# bontor_mbed_rev_e.net
KiCad netlist of a schematic drawn in EAGLE
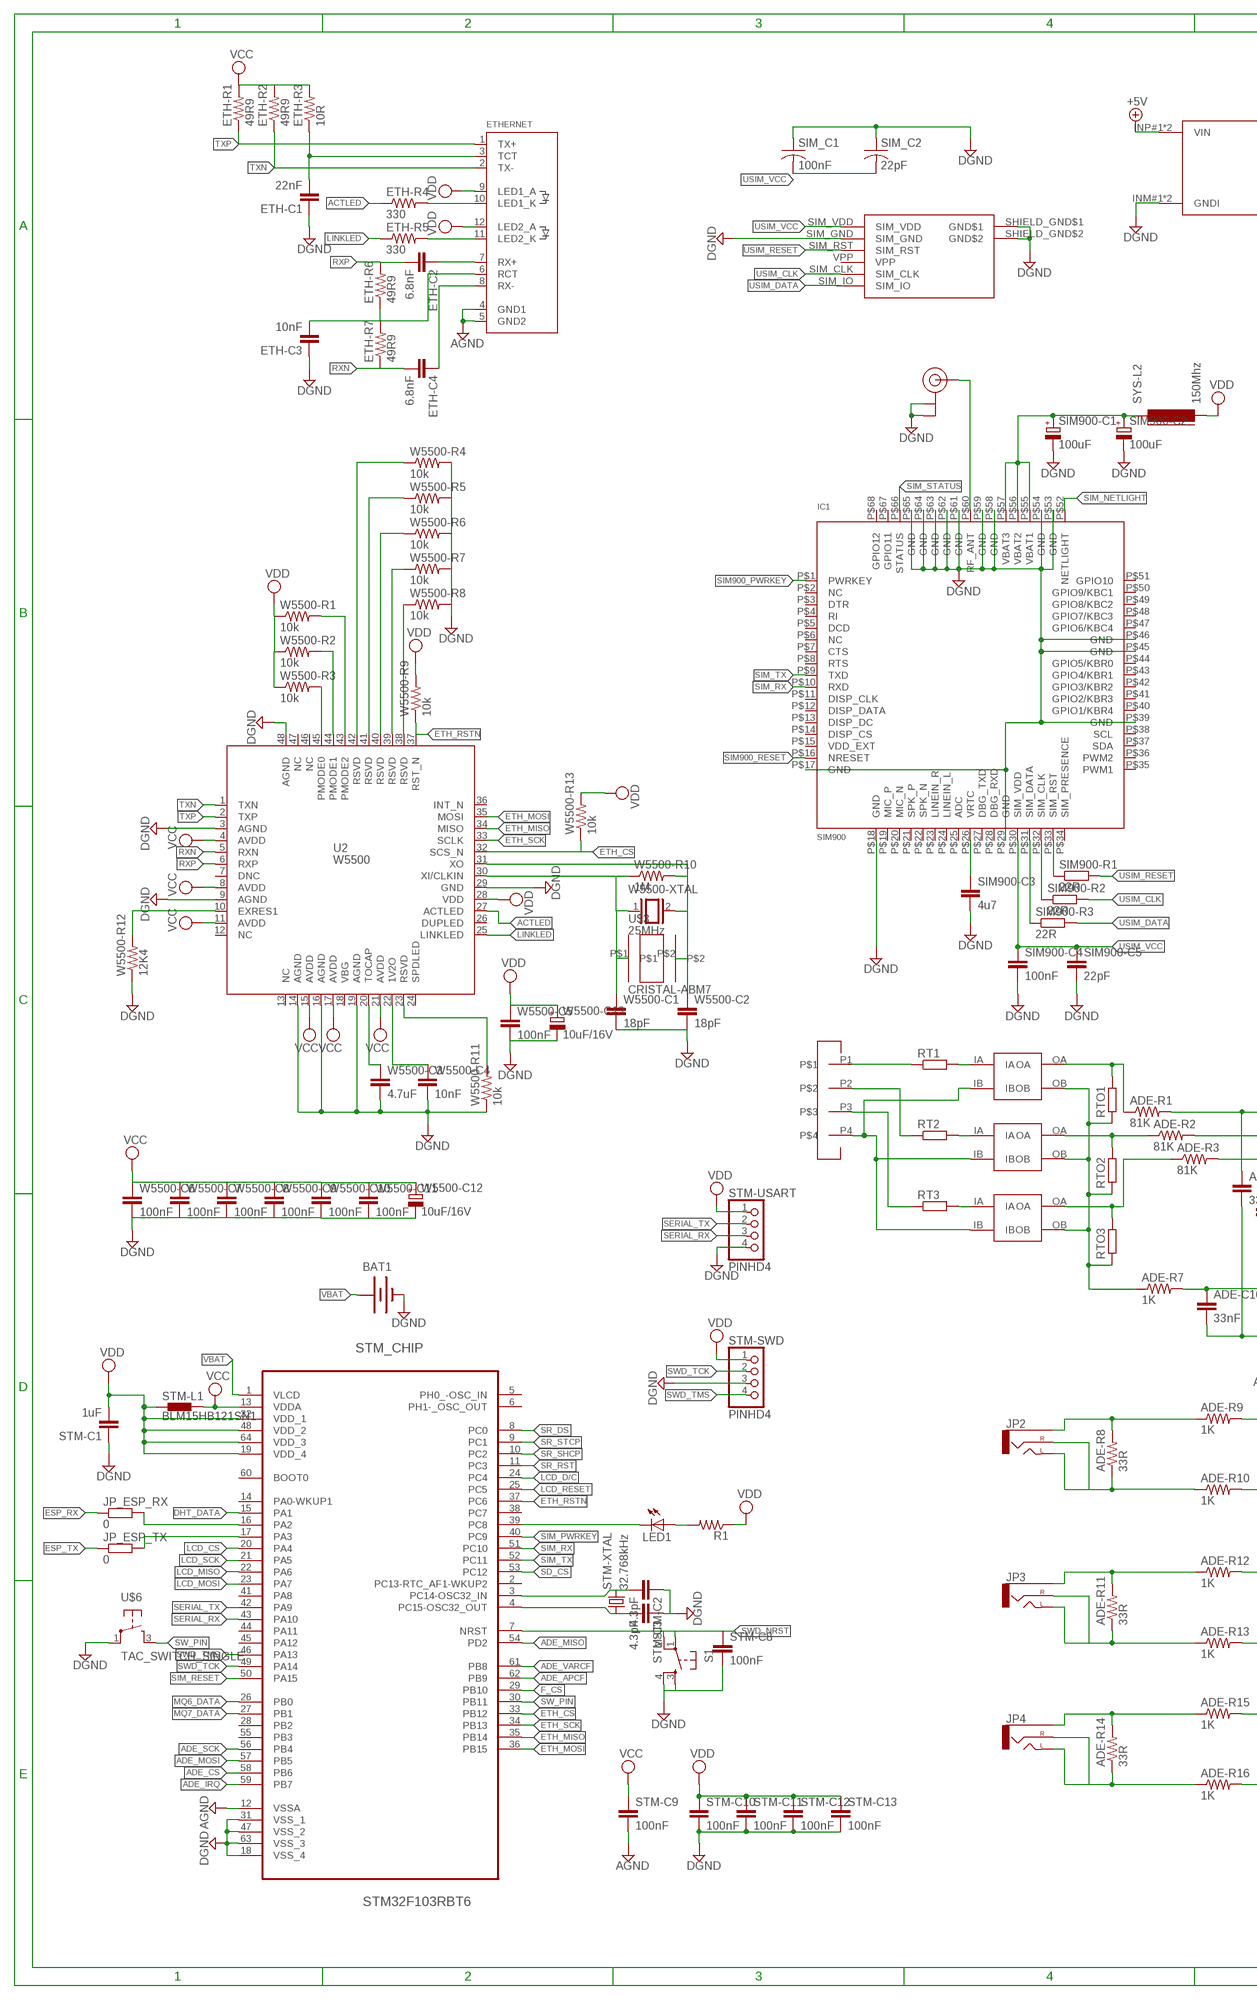
[diagram p0: schematic, sheet 1, part 1 of 2]
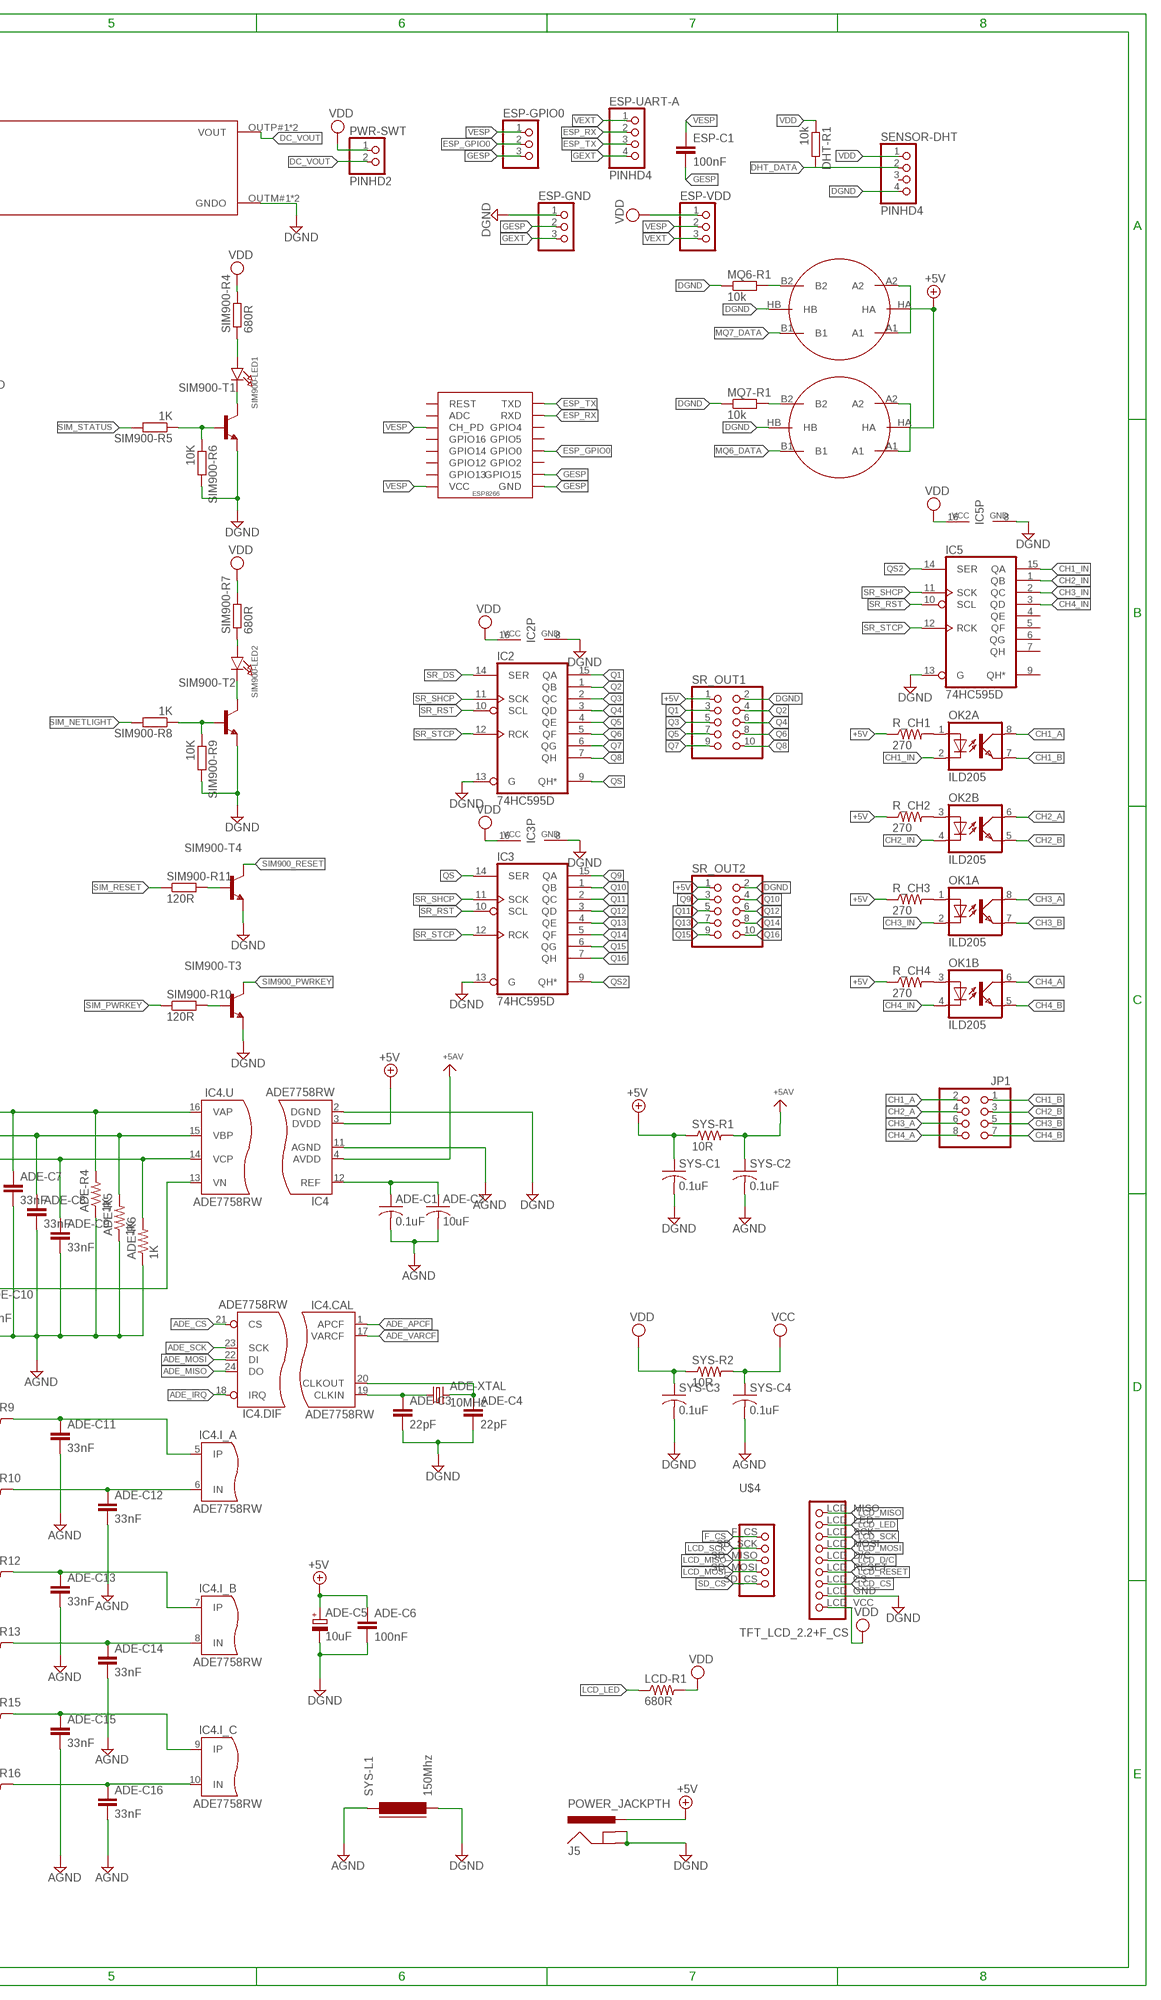
[diagram p1: schematic, sheet 1, part 2 of 2]

(export (version "E")
  (design (tool "Eeschema 10.0.6"))
  (components
    (comp (ref "ADE-C1")
      (value "0.1uF")
      (footprint "eagle-import:C0603@1")
      (libsource (lib "eagle-import") (part "C-USC0603"))
    )
    (comp (ref "ADE-C2")
      (value "10uF")
      (footprint "eagle-import:C0805K")
      (libsource (lib "eagle-import") (part "C-USC0805K"))
    )
    (comp (ref "ADE-C3")
      (value "22pF")
      (footprint "eagle-import:C0603")
      (libsource (lib "eagle-import") (part "C-EUC0603"))
    )
    (comp (ref "ADE-C4")
      (value "22pF")
      (footprint "eagle-import:C0603")
      (libsource (lib "eagle-import") (part "C-EUC0603"))
    )
    (comp (ref "ADE-C5")
      (value "10uF")
      (footprint "eagle-import:153CLV-0605")
      (libsource (lib "eagle-import") (part "CPOL-EU153CLV-0605"))
    )
    (comp (ref "ADE-C6")
      (value "100nF")
      (footprint "eagle-import:C0603")
      (libsource (lib "eagle-import") (part "C-EUC0603"))
    )
    (comp (ref "ADE-C7")
      (value "33nF")
      (footprint "eagle-import:0603-CAP")
      (libsource (lib "eagle-import") (part "CAP0603-CAP"))
    )
    (comp (ref "ADE-C8")
      (value "33nF")
      (footprint "eagle-import:0603-CAP")
      (libsource (lib "eagle-import") (part "CAP0603-CAP"))
    )
    (comp (ref "ADE-C9")
      (value "33nF")
      (footprint "eagle-import:0603-CAP")
      (libsource (lib "eagle-import") (part "CAP0603-CAP"))
    )
    (comp (ref "ADE-C10")
      (value "33nF")
      (footprint "eagle-import:0603-CAP")
      (libsource (lib "eagle-import") (part "CAP0603-CAP"))
    )
    (comp (ref "ADE-C11")
      (value "33nF")
      (footprint "eagle-import:0603-CAP")
      (libsource (lib "eagle-import") (part "CAP0603-CAP"))
    )
    (comp (ref "ADE-C12")
      (value "33nF")
      (footprint "eagle-import:0603-CAP")
      (libsource (lib "eagle-import") (part "CAP0603-CAP"))
    )
    (comp (ref "ADE-C13")
      (value "33nF")
      (footprint "eagle-import:0603-CAP")
      (libsource (lib "eagle-import") (part "CAP0603-CAP"))
    )
    (comp (ref "ADE-C14")
      (value "33nF")
      (footprint "eagle-import:0603-CAP")
      (libsource (lib "eagle-import") (part "CAP0603-CAP"))
    )
    (comp (ref "ADE-C15")
      (value "33nF")
      (footprint "eagle-import:0603-CAP")
      (libsource (lib "eagle-import") (part "CAP0603-CAP"))
    )
    (comp (ref "ADE-C16")
      (value "33nF")
      (footprint "eagle-import:0603-CAP")
      (libsource (lib "eagle-import") (part "CAP0603-CAP"))
    )
    (comp (ref "ADE-R1")
      (value "81K")
      (footprint "eagle-import:0603-RES")
      (libsource (lib "eagle-import") (part "SparkFun-Passives_RESISTOR0603-RES"))
    )
    (comp (ref "ADE-R2")
      (value "81K")
      (footprint "eagle-import:0603-RES")
      (libsource (lib "eagle-import") (part "SparkFun-Passives_RESISTOR0603-RES"))
    )
    (comp (ref "ADE-R3")
      (value "81K")
      (footprint "eagle-import:0603-RES")
      (libsource (lib "eagle-import") (part "SparkFun-Passives_RESISTOR0603-RES"))
    )
    (comp (ref "ADE-R4")
      (value "1K")
      (footprint "eagle-import:0603-RES")
      (libsource (lib "eagle-import") (part "SparkFun-Passives_RESISTOR0603-RES"))
    )
    (comp (ref "ADE-R5")
      (value "1K")
      (footprint "eagle-import:0603-RES")
      (libsource (lib "eagle-import") (part "SparkFun-Passives_RESISTOR0603-RES"))
    )
    (comp (ref "ADE-R6")
      (value "1K")
      (footprint "eagle-import:0603-RES")
      (libsource (lib "eagle-import") (part "SparkFun-Passives_RESISTOR0603-RES"))
    )
    (comp (ref "ADE-R7")
      (value "1K")
      (footprint "eagle-import:0603-RES")
      (libsource (lib "eagle-import") (part "SparkFun-Passives_RESISTOR0603-RES"))
    )
    (comp (ref "ADE-R8")
      (value "33R")
      (footprint "eagle-import:0603-RES")
      (libsource (lib "eagle-import") (part "SparkFun-Passives_RESISTOR0603-RES"))
    )
    (comp (ref "ADE-R9")
      (value "1K")
      (footprint "eagle-import:0603-RES")
      (libsource (lib "eagle-import") (part "SparkFun-Passives_RESISTOR0603-RES"))
    )
    (comp (ref "ADE-R10")
      (value "1K")
      (footprint "eagle-import:0603-RES")
      (libsource (lib "eagle-import") (part "SparkFun-Passives_RESISTOR0603-RES"))
    )
    (comp (ref "ADE-R11")
      (value "33R")
      (footprint "eagle-import:0603-RES")
      (libsource (lib "eagle-import") (part "SparkFun-Passives_RESISTOR0603-RES"))
    )
    (comp (ref "ADE-R12")
      (value "1K")
      (footprint "eagle-import:0603-RES")
      (libsource (lib "eagle-import") (part "SparkFun-Passives_RESISTOR0603-RES"))
    )
    (comp (ref "ADE-R13")
      (value "1K")
      (footprint "eagle-import:0603-RES")
      (libsource (lib "eagle-import") (part "SparkFun-Passives_RESISTOR0603-RES"))
    )
    (comp (ref "ADE-R14")
      (value "33R")
      (footprint "eagle-import:0603-RES")
      (libsource (lib "eagle-import") (part "SparkFun-Passives_RESISTOR0603-RES"))
    )
    (comp (ref "ADE-R15")
      (value "1K")
      (footprint "eagle-import:0603-RES")
      (libsource (lib "eagle-import") (part "SparkFun-Passives_RESISTOR0603-RES"))
    )
    (comp (ref "ADE-R16")
      (value "1K")
      (footprint "eagle-import:0603-RES")
      (libsource (lib "eagle-import") (part "SparkFun-Passives_RESISTOR0603-RES"))
    )
    (comp (ref "ADE-XTAL")
      (value "10MHz")
      (footprint "eagle-import:HC49US")
      (libsource (lib "eagle-import") (part "CRYSTALHC49US"))
    )
    (comp (ref "BAT1")
      (value "BATTERY20PTH")
      (footprint "eagle-import:BATTCOM_20MM_PTH")
      (libsource (lib "eagle-import") (part "BATTERY20PTH"))
    )
    (comp (ref "DCDC-3.5V")
      (value "DCDCMODULE_SMALL")
      (footprint "eagle-import:DCDCMODULE-SMALL")
      (libsource (lib "eagle-import") (part "DCDCMODULE_SMALL"))
    )
    (comp (ref "DHT-R1")
      (value "10k")
      (footprint "eagle-import:R0603")
      (libsource (lib "eagle-import") (part "resistor_R-EU_R0603"))
    )
    (comp (ref "ESP-C1")
      (value "100nF")
      (footprint "eagle-import:C0603")
      (libsource (lib "eagle-import") (part "C-EUC0603"))
    )
    (comp (ref "ESP-GND")
      (value "PINHD-1X3")
      (footprint "eagle-import:1X03")
      (libsource (lib "eagle-import") (part "PINHD-1X3"))
    )
    (comp (ref "ESP-GPIO0")
      (value "PINHD-1X3")
      (footprint "eagle-import:1X03")
      (libsource (lib "eagle-import") (part "PINHD-1X3"))
    )
    (comp (ref "ESP-UART-A")
      (value "PINHD4")
      (footprint "eagle-import:PINHD4")
      (libsource (lib "eagle-import") (part "PINHD4"))
    )
    (comp (ref "ESP-VDD")
      (value "PINHD-1X3")
      (footprint "eagle-import:1X03")
      (libsource (lib "eagle-import") (part "PINHD-1X3"))
    )
    (comp (ref "ETH-C1")
      (value "22nF")
      (footprint "eagle-import:C0603")
      (libsource (lib "eagle-import") (part "C-EUC0603"))
    )
    (comp (ref "ETH-C2")
      (value "6.8nF")
      (footprint "eagle-import:C0603")
      (libsource (lib "eagle-import") (part "C-EUC0603"))
    )
    (comp (ref "ETH-C3")
      (value "10nF")
      (footprint "eagle-import:C0603")
      (libsource (lib "eagle-import") (part "C-EUC0603"))
    )
    (comp (ref "ETH-C4")
      (value "6.8nF")
      (footprint "eagle-import:C0603")
      (libsource (lib "eagle-import") (part "C-EUC0603"))
    )
    (comp (ref "ETH-R1")
      (value "49R9")
      (footprint "eagle-import:R0603")
      (libsource (lib "eagle-import") (part "R-US_R0603"))
    )
    (comp (ref "ETH-R2")
      (value "49R9")
      (footprint "eagle-import:R0603")
      (libsource (lib "eagle-import") (part "R-US_R0603"))
    )
    (comp (ref "ETH-R3")
      (value "10R")
      (footprint "eagle-import:R0603")
      (libsource (lib "eagle-import") (part "R-US_R0603"))
    )
    (comp (ref "ETH-R4")
      (value "330")
      (footprint "eagle-import:R0603")
      (libsource (lib "eagle-import") (part "R-US_R0603"))
    )
    (comp (ref "ETH-R5")
      (value "330")
      (footprint "eagle-import:R0603")
      (libsource (lib "eagle-import") (part "R-US_R0603"))
    )
    (comp (ref "ETH-R6")
      (value "49R9")
      (footprint "eagle-import:R0603")
      (libsource (lib "eagle-import") (part "R-US_R0603"))
    )
    (comp (ref "ETH-R7")
      (value "49R9")
      (footprint "eagle-import:R0603")
      (libsource (lib "eagle-import") (part "R-US_R0603"))
    )
    (comp (ref "ETHERNET")
      (value "RJ45J0026D21BNL")
      (footprint "eagle-import:RJ45_PULSEJACK")
      (libsource (lib "eagle-import") (part "RJ45J0026D21BNL"))
    )
    (comp (ref "IC1")
      (value "SIM900")
      (footprint "eagle-import:SIM900_SMT")
      (libsource (lib "eagle-import") (part "GSM_SIM900_LITERAL"))
    )
    (comp (ref "IC2")
      (value "74HC595D")
      (footprint "eagle-import:SO16")
      (libsource (lib "eagle-import") (part "74595DHC"))
    )
    (comp (ref "IC3")
      (value "74HC595D")
      (footprint "eagle-import:SO16")
      (libsource (lib "eagle-import") (part "74595DHC"))
    )
    (comp (ref "IC4")
      (value "ADE7758RW")
      (footprint "eagle-import:SOIC24")
      (libsource (lib "eagle-import") (part "ADE7758RW"))
    )
    (comp (ref "IC5")
      (value "74HC595D")
      (footprint "eagle-import:SO16")
      (libsource (lib "eagle-import") (part "74595DHC"))
    )
    (comp (ref "J5")
      (value "POWER_JACKPTH")
      (footprint "eagle-import:POWER_JACK_PTH")
      (libsource (lib "eagle-import") (part "POWER_JACKPTH"))
    )
    (comp (ref "JP1")
      (value "PINHD-2X4")
      (footprint "eagle-import:2X04")
      (libsource (lib "eagle-import") (part "PINHD-2X4"))
    )
    (comp (ref "JP2")
      (value "AUDIO-JACKSMD2")
      (footprint "eagle-import:AUDIO-JACK-3.5MM-SMD")
      (libsource (lib "eagle-import") (part "AUDIO-JACKSMD2"))
    )
    (comp (ref "JP3")
      (value "AUDIO-JACKSMD2")
      (footprint "eagle-import:AUDIO-JACK-3.5MM-SMD")
      (libsource (lib "eagle-import") (part "AUDIO-JACKSMD2"))
    )
    (comp (ref "JP4")
      (value "AUDIO-JACKSMD2")
      (footprint "eagle-import:AUDIO-JACK-3.5MM-SMD")
      (libsource (lib "eagle-import") (part "AUDIO-JACKSMD2"))
    )
    (comp (ref "JP_ESP_RX")
      (value "0")
      (footprint "eagle-import:R0201")
      (libsource (lib "eagle-import") (part "R-EU_R0201"))
    )
    (comp (ref "JP_ESP_TX")
      (value "0")
      (footprint "eagle-import:R0201")
      (libsource (lib "eagle-import") (part "R-EU_R0201"))
    )
    (comp (ref "LCD-R1")
      (value "680R")
      (footprint "eagle-import:0603-RES")
      (libsource (lib "eagle-import") (part "SparkFun-Passives_RESISTOR0603-RES"))
    )
    (comp (ref "LED1")
      (value "LEDCHIPLED_0603")
      (footprint "eagle-import:CHIPLED_0603")
      (libsource (lib "eagle-import") (part "LEDCHIPLED_0603"))
    )
    (comp (ref "MQ6-R1")
      (value "10k")
      (footprint "eagle-import:R0603")
      (libsource (lib "eagle-import") (part "resistor_R-EU_R0603"))
    )
    (comp (ref "MQ7-R1")
      (value "10k")
      (footprint "eagle-import:R0603")
      (libsource (lib "eagle-import") (part "resistor_R-EU_R0603"))
    )
    (comp (ref "OK1")
      (value "ILD205")
      (footprint "eagle-import:SOIC08")
      (fields (field (name "MF") "VISHAY/TELEFUNKEN") (field (name "MPN") "ILD205T"))
      (libsource (lib "eagle-import") (part "ILD205"))
    )
    (comp (ref "OK2")
      (value "ILD205")
      (footprint "eagle-import:SOIC08")
      (fields (field (name "MF") "VISHAY/TELEFUNKEN") (field (name "MPN") "ILD205T"))
      (libsource (lib "eagle-import") (part "ILD205"))
    )
    (comp (ref "PWR-SWT")
      (value "PINHD2")
      (footprint "eagle-import:PINHD2")
      (libsource (lib "eagle-import") (part "PINHD2"))
    )
    (comp (ref "R1")
      (value "RESISTOR0603-RES")
      (footprint "eagle-import:0603-RES")
      (libsource (lib "eagle-import") (part "RESISTOR0603-RES"))
    )
    (comp (ref "RT1")
      (value "R-EU_0309/V")
      (footprint "eagle-import:0309V")
      (libsource (lib "eagle-import") (part "R-EU_0309/V"))
    )
    (comp (ref "RT2")
      (value "R-EU_0309/V")
      (footprint "eagle-import:0309V")
      (libsource (lib "eagle-import") (part "R-EU_0309/V"))
    )
    (comp (ref "RT3")
      (value "R-EU_0309/V")
      (footprint "eagle-import:0309V")
      (libsource (lib "eagle-import") (part "R-EU_0309/V"))
    )
    (comp (ref "RTO1")
      (value "R-EU_0309/12")
      (footprint "eagle-import:0309_12")
      (libsource (lib "eagle-import") (part "R-EU_0309/12"))
    )
    (comp (ref "RTO2")
      (value "R-EU_0309/12")
      (footprint "eagle-import:0309_12")
      (libsource (lib "eagle-import") (part "R-EU_0309/12"))
    )
    (comp (ref "RTO3")
      (value "R-EU_0309/12")
      (footprint "eagle-import:0309_12")
      (libsource (lib "eagle-import") (part "R-EU_0309/12"))
    )
    (comp (ref "R_CH1")
      (value "270")
      (footprint "eagle-import:0603-RES")
      (libsource (lib "eagle-import") (part "SparkFun-Passives_RESISTOR0603-RES"))
    )
    (comp (ref "R_CH2")
      (value "270")
      (footprint "eagle-import:0603-RES")
      (libsource (lib "eagle-import") (part "SparkFun-Passives_RESISTOR0603-RES"))
    )
    (comp (ref "R_CH3")
      (value "270")
      (footprint "eagle-import:0603-RES")
      (libsource (lib "eagle-import") (part "SparkFun-Passives_RESISTOR0603-RES"))
    )
    (comp (ref "R_CH4")
      (value "270")
      (footprint "eagle-import:0603-RES")
      (libsource (lib "eagle-import") (part "SparkFun-Passives_RESISTOR0603-RES"))
    )
    (comp (ref "S1")
      (value "TAC_SWITCHPTH")
      (footprint "eagle-import:TACTILE-PTH")
      (libsource (lib "eagle-import") (part "TAC_SWITCHPTH"))
    )
    (comp (ref "SENSOR-DHT")
      (value "PINHD4")
      (footprint "eagle-import:PINHD4")
      (libsource (lib "eagle-import") (part "PINHD4"))
    )
    (comp (ref "SENSOR-MQ6")
      (value "METHANE_SENSOR")
      (footprint "eagle-import:MQ-3")
      (libsource (lib "eagle-import") (part "METHANE_SENSOR"))
    )
    (comp (ref "SENSOR-MQ7")
      (value "METHANE_SENSOR")
      (footprint "eagle-import:MQ-3")
      (libsource (lib "eagle-import") (part "METHANE_SENSOR"))
    )
    (comp (ref "SIM900-C1")
      (value "100uF")
      (footprint "eagle-import:153CLV-0605")
      (libsource (lib "eagle-import") (part "CPOL-EU153CLV-0605"))
    )
    (comp (ref "SIM900-C2")
      (value "100uF")
      (footprint "eagle-import:153CLV-0605")
      (libsource (lib "eagle-import") (part "CPOL-EU153CLV-0605"))
    )
    (comp (ref "SIM900-C3")
      (value "4u7")
      (footprint "eagle-import:C0603")
      (libsource (lib "eagle-import") (part "C-EUC0603"))
    )
    (comp (ref "SIM900-C4")
      (value "100nF")
      (footprint "eagle-import:C0603")
      (libsource (lib "eagle-import") (part "C-EUC0603"))
    )
    (comp (ref "SIM900-C5")
      (value "22pF")
      (footprint "eagle-import:C0603")
      (libsource (lib "eagle-import") (part "C-EUC0603"))
    )
    (comp (ref "SIM900-LED1")
      (value "LED0805_NOOUTLINE")
      (footprint "eagle-import:CHIPLED_0805_NOOUTLINE")
      (libsource (lib "eagle-import") (part "LED0805_NOOUTLINE"))
    )
    (comp (ref "SIM900-LED2")
      (value "LED0805_NOOUTLINE")
      (footprint "eagle-import:CHIPLED_0805_NOOUTLINE")
      (libsource (lib "eagle-import") (part "LED0805_NOOUTLINE"))
    )
    (comp (ref "SIM900-R1")
      (value "22R")
      (footprint "eagle-import:R0603")
      (libsource (lib "eagle-import") (part "R-EU_R0603"))
    )
    (comp (ref "SIM900-R2")
      (value "22R")
      (footprint "eagle-import:R0603")
      (libsource (lib "eagle-import") (part "R-EU_R0603"))
    )
    (comp (ref "SIM900-R3")
      (value "22R")
      (footprint "eagle-import:R0603")
      (libsource (lib "eagle-import") (part "R-EU_R0603"))
    )
    (comp (ref "SIM900-R4")
      (value "680R")
      (footprint "eagle-import:R0603")
      (libsource (lib "eagle-import") (part "R-EU_R0603"))
    )
    (comp (ref "SIM900-R5")
      (value "1K")
      (footprint "eagle-import:R0603")
      (libsource (lib "eagle-import") (part "R-EU_R0603"))
    )
    (comp (ref "SIM900-R6")
      (value "10K")
      (footprint "eagle-import:R0603")
      (libsource (lib "eagle-import") (part "R-EU_R0603"))
    )
    (comp (ref "SIM900-R7")
      (value "680R")
      (footprint "eagle-import:R0603")
      (libsource (lib "eagle-import") (part "R-EU_R0603"))
    )
    (comp (ref "SIM900-R8")
      (value "1K")
      (footprint "eagle-import:R0603")
      (libsource (lib "eagle-import") (part "R-EU_R0603"))
    )
    (comp (ref "SIM900-R9")
      (value "10K")
      (footprint "eagle-import:R0603")
      (libsource (lib "eagle-import") (part "R-EU_R0603"))
    )
    (comp (ref "SIM900-R10")
      (value "120R")
      (footprint "eagle-import:R0603")
      (libsource (lib "eagle-import") (part "resistor_R-EU_R0603"))
    )
    (comp (ref "SIM900-R11")
      (value "120R")
      (footprint "eagle-import:R0603")
      (libsource (lib "eagle-import") (part "resistor_R-EU_R0603"))
    )
    (comp (ref "SIM900-T1")
      (value "MMBT2222ALT1-NPN-SOT23-BEC")
      (footprint "eagle-import:SOT23-BEC")
      (libsource (lib "eagle-import") (part "-NPN-SOT23-BECMMBT2222ALT1"))
    )
    (comp (ref "SIM900-T2")
      (value "MMBT2222ALT1-NPN-SOT23-BEC")
      (footprint "eagle-import:SOT23-BEC")
      (libsource (lib "eagle-import") (part "-NPN-SOT23-BECMMBT2222ALT1"))
    )
    (comp (ref "SIM900-T3")
      (value "MMBT2222ALT1-NPN-SOT23-BEC")
      (footprint "eagle-import:SOT23-BEC")
      (libsource (lib "eagle-import") (part "transistor-neu-to92_-NPN-SOT23-BECMMBT2222ALT1"))
    )
    (comp (ref "SIM900-T4")
      (value "MMBT2222ALT1-NPN-SOT23-BEC")
      (footprint "eagle-import:SOT23-BEC")
      (libsource (lib "eagle-import") (part "transistor-neu-to92_-NPN-SOT23-BECMMBT2222ALT1"))
    )
    (comp (ref "SIM_C1")
      (value "100nF")
      (footprint "eagle-import:C0603K")
      (libsource (lib "eagle-import") (part "C-USC0603K"))
    )
    (comp (ref "SIM_C2")
      (value "22pF")
      (footprint "eagle-import:C0603K")
      (libsource (lib "eagle-import") (part "C-USC0603K"))
    )
    (comp (ref "SR_OUT1")
      (value "PINHD-2X5/90")
      (footprint "eagle-import:2X05_90")
      (libsource (lib "eagle-import") (part "PINHD-2X5/90"))
    )
    (comp (ref "SR_OUT2")
      (value "PINHD-2X5/90")
      (footprint "eagle-import:2X05_90")
      (libsource (lib "eagle-import") (part "PINHD-2X5/90"))
    )
    (comp (ref "STM-C1")
      (value "1uF")
      (footprint "eagle-import:C0603")
      (libsource (lib "eagle-import") (part "C-EUC0603"))
    )
    (comp (ref "STM-C2")
      (value "4.3pF")
      (footprint "eagle-import:C0603")
      (libsource (lib "eagle-import") (part "C-EUC0603"))
    )
    (comp (ref "STM-C3")
      (value "4.3pF")
      (footprint "eagle-import:C0603")
      (libsource (lib "eagle-import") (part "C-EUC0603"))
    )
    (comp (ref "STM-C8")
      (value "100nF")
      (footprint "eagle-import:C0603")
      (libsource (lib "eagle-import") (part "C-EUC0603"))
    )
    (comp (ref "STM-C9")
      (value "100nF")
      (footprint "eagle-import:C0603")
      (libsource (lib "eagle-import") (part "C-EUC0603"))
    )
    (comp (ref "STM-C10")
      (value "100nF")
      (footprint "eagle-import:C0603")
      (libsource (lib "eagle-import") (part "C-EUC0603"))
    )
    (comp (ref "STM-C11")
      (value "100nF")
      (footprint "eagle-import:C0603")
      (libsource (lib "eagle-import") (part "C-EUC0603"))
    )
    (comp (ref "STM-C12")
      (value "100nF")
      (footprint "eagle-import:C0603")
      (libsource (lib "eagle-import") (part "C-EUC0603"))
    )
    (comp (ref "STM-C13")
      (value "100nF")
      (footprint "eagle-import:C0603")
      (libsource (lib "eagle-import") (part "C-EUC0603"))
    )
    (comp (ref "STM-L1")
      (value "BLM15HB121SN1")
      (footprint "eagle-import:0402")
      (libsource (lib "eagle-import") (part "BLM15HB121SN1"))
    )
    (comp (ref "STM-SWD")
      (value "PINHD4")
      (footprint "eagle-import:PINHD4")
      (libsource (lib "eagle-import") (part "PINHD4"))
    )
    (comp (ref "STM-USART")
      (value "PINHD4")
      (footprint "eagle-import:PINHD4")
      (libsource (lib "eagle-import") (part "PINHD4"))
    )
    (comp (ref "STM-XTAL")
      (value "32.768kHz")
      (footprint "eagle-import:TC26H")
      (libsource (lib "eagle-import") (part "CRYSTALTC26H"))
    )
    (comp (ref "STM_CHIP")
      (value "STM32F103RBT6")
      (footprint "eagle-import:QFP50P1200X1200X160-64N")
      (fields (field (name "MPN") "STM32L152RBT6"))
      (libsource (lib "eagle-import") (part "STM32L152RBT6"))
    )
    (comp (ref "SYS-C1")
      (value "0.1uF")
      (footprint "eagle-import:C0603@1")
      (libsource (lib "eagle-import") (part "C-USC0603"))
    )
    (comp (ref "SYS-C2")
      (value "0.1uF")
      (footprint "eagle-import:C0603@1")
      (libsource (lib "eagle-import") (part "C-USC0603"))
    )
    (comp (ref "SYS-C3")
      (value "0.1uF")
      (footprint "eagle-import:C0603@1")
      (libsource (lib "eagle-import") (part "C-USC0603"))
    )
    (comp (ref "SYS-C4")
      (value "0.1uF")
      (footprint "eagle-import:C0603@1")
      (libsource (lib "eagle-import") (part "C-USC0603"))
    )
    (comp (ref "SYS-L1")
      (value "150Mhz")
      (footprint "eagle-import:FB805")
      (libsource (lib "eagle-import") (part "FERRITE-0805"))
    )
    (comp (ref "SYS-L2")
      (value "150Mhz")
      (footprint "eagle-import:FB805")
      (libsource (lib "eagle-import") (part "FERRITE-0805"))
    )
    (comp (ref "SYS-R1")
      (value "10R")
      (footprint "eagle-import:0603-RES")
      (libsource (lib "eagle-import") (part "SparkFun-Passives_RESISTOR0603-RES"))
    )
    (comp (ref "SYS-R2")
      (value "10R")
      (footprint "eagle-import:0603-RES")
      (libsource (lib "eagle-import") (part "SparkFun-Passives_RESISTOR0603-RES"))
    )
    (comp (ref "U$3")
      (value "CRISTAL-ABM7")
      (footprint "eagle-import:CRISTAL-ABM7")
      (libsource (lib "eagle-import") (part "CRISTAL-ABM7"))
    )
    (comp (ref "U$4")
      (value "TFT_LCD_2.2+F_CS")
      (footprint "eagle-import:TFT_LCD_2.2+F_CS")
      (libsource (lib "eagle-import") (part "TFT_LCD_2.2+F_CS"))
    )
    (comp (ref "U$5")
      (value "ESP8266WI12")
      (footprint "eagle-import:WI12")
      (libsource (lib "eagle-import") (part "ESP8266WI12"))
    )
    (comp (ref "U$6")
      (value "TAC_SWITCH_SINGLE")
      (footprint "eagle-import:TACTILE-PTH-SINGLE")
      (libsource (lib "eagle-import") (part "TAC_SWITCH_SINGLE"))
    )
    (comp (ref "U$7")
      (value "U.FL")
      (footprint "eagle-import:U.FL")
      (libsource (lib "eagle-import") (part "U.FL"))
    )
    (comp (ref "U$8")
      (value "SIM_HOLDER")
      (footprint "eagle-import:SIMHOLDER-PUSHPUSH")
      (libsource (lib "eagle-import") (part "SIM_HOLDER"))
    )
    (comp (ref "U$9")
      (value "TRANSFORMER")
      (footprint "eagle-import:TV16")
      (libsource (lib "eagle-import") (part "TRANSFORMER"))
    )
    (comp (ref "U$10")
      (value "TRANSFORMER")
      (footprint "eagle-import:TV16")
      (libsource (lib "eagle-import") (part "TRANSFORMER"))
    )
    (comp (ref "U$11")
      (value "TRANSFORMER")
      (footprint "eagle-import:TV16")
      (libsource (lib "eagle-import") (part "TRANSFORMER"))
    )
    (comp (ref "U$12")
      (value "TERMINAL_BLOCK")
      (footprint "eagle-import:TERMINAL-RIGHT-ANGLE")
      (libsource (lib "eagle-import") (part "TERMINAL_BLOCK"))
    )
    (comp (ref "U2")
      (value "W5500")
      (footprint "eagle-import:W5500")
      (libsource (lib "eagle-import") (part "W5500"))
    )
    (comp (ref "W5500-C1")
      (value "18pF")
      (footprint "eagle-import:C0603")
      (libsource (lib "eagle-import") (part "C-EUC0603"))
    )
    (comp (ref "W5500-C2")
      (value "18pF")
      (footprint "eagle-import:C0603")
      (libsource (lib "eagle-import") (part "C-EUC0603"))
    )
    (comp (ref "W5500-C3")
      (value "4.7uF")
      (footprint "eagle-import:C0603")
      (libsource (lib "eagle-import") (part "C-EUC0603"))
    )
    (comp (ref "W5500-C4")
      (value "10nF")
      (footprint "eagle-import:C0603")
      (libsource (lib "eagle-import") (part "C-EUC0603"))
    )
    (comp (ref "W5500-C5")
      (value "100nF")
      (footprint "eagle-import:C0603")
      (libsource (lib "eagle-import") (part "C-EUC0603"))
    )
    (comp (ref "W5500-C6")
      (value "100nF")
      (footprint "eagle-import:C0603")
      (libsource (lib "eagle-import") (part "C-EUC0603"))
    )
    (comp (ref "W5500-C7")
      (value "100nF")
      (footprint "eagle-import:C0603")
      (libsource (lib "eagle-import") (part "C-EUC0603"))
    )
    (comp (ref "W5500-C8")
      (value "100nF")
      (footprint "eagle-import:C0603")
      (libsource (lib "eagle-import") (part "C-EUC0603"))
    )
    (comp (ref "W5500-C9")
      (value "100nF")
      (footprint "eagle-import:C0603")
      (libsource (lib "eagle-import") (part "C-EUC0603"))
    )
    (comp (ref "W5500-C10")
      (value "100nF")
      (footprint "eagle-import:C0603")
      (libsource (lib "eagle-import") (part "C-EUC0603"))
    )
    (comp (ref "W5500-C11")
      (value "100nF")
      (footprint "eagle-import:C0603")
      (libsource (lib "eagle-import") (part "C-EUC0603"))
    )
    (comp (ref "W5500-C12")
      (value "10uF/16V")
      (footprint "eagle-import:153CLV-0605")
      (libsource (lib "eagle-import") (part "CPOL-EU153CLV-0605"))
    )
    (comp (ref "W5500-C13")
      (value "10uF/16V")
      (footprint "eagle-import:153CLV-0605")
      (libsource (lib "eagle-import") (part "CPOL-EU153CLV-0605"))
    )
    (comp (ref "W5500-R1")
      (value "10k")
      (footprint "eagle-import:R0603")
      (libsource (lib "eagle-import") (part "R-US_R0603"))
    )
    (comp (ref "W5500-R2")
      (value "10k")
      (footprint "eagle-import:R0603")
      (libsource (lib "eagle-import") (part "R-US_R0603"))
    )
    (comp (ref "W5500-R3")
      (value "10k")
      (footprint "eagle-import:R0603")
      (libsource (lib "eagle-import") (part "R-US_R0603"))
    )
    (comp (ref "W5500-R4")
      (value "10k")
      (footprint "eagle-import:R0603")
      (libsource (lib "eagle-import") (part "R-US_R0603"))
    )
    (comp (ref "W5500-R5")
      (value "10k")
      (footprint "eagle-import:R0603")
      (libsource (lib "eagle-import") (part "R-US_R0603"))
    )
    (comp (ref "W5500-R6")
      (value "10k")
      (footprint "eagle-import:R0603")
      (libsource (lib "eagle-import") (part "R-US_R0603"))
    )
    (comp (ref "W5500-R7")
      (value "10k")
      (footprint "eagle-import:R0603")
      (libsource (lib "eagle-import") (part "R-US_R0603"))
    )
    (comp (ref "W5500-R8")
      (value "10k")
      (footprint "eagle-import:R0603")
      (libsource (lib "eagle-import") (part "R-US_R0603"))
    )
    (comp (ref "W5500-R9")
      (value "10k")
      (footprint "eagle-import:R0603")
      (libsource (lib "eagle-import") (part "R-US_R0603"))
    )
    (comp (ref "W5500-R10")
      (value "1M")
      (footprint "eagle-import:R0603")
      (libsource (lib "eagle-import") (part "R-US_R0603"))
    )
    (comp (ref "W5500-R11")
      (value "10k")
      (footprint "eagle-import:R0603")
      (libsource (lib "eagle-import") (part "R-US_R0603"))
    )
    (comp (ref "W5500-R12")
      (value "12K4")
      (footprint "eagle-import:R0805")
      (libsource (lib "eagle-import") (part "R-US_R0805"))
    )
    (comp (ref "W5500-R13")
      (value "10k")
      (footprint "eagle-import:R0603")
      (libsource (lib "eagle-import") (part "R-US_R0603"))
    )
    (comp (ref "W5500-XTAL")
      (value "25MHz")
      (footprint "eagle-import:QS")
      (libsource (lib "eagle-import") (part "XTAL/S"))
    )
  )
  (nets
    (net (code "1") (name "+5AV") (class "Default")
      (node (ref "IC4") (pin "4") (pinfunction "AVDD_4") (pintype "power_in"))
      (node (ref "SYS-C2") (pin "1") (pinfunction "1_1") (pintype "passive"))
      (node (ref "SYS-R1") (pin "2") (pinfunction "2_2") (pintype "passive"))
    )
    (net (code "2") (name "+5V") (class "Default")
      (node (ref "ADE-C5") (pin "+") (pinfunction "+_+") (pintype "passive"))
      (node (ref "ADE-C6") (pin "1") (pinfunction "1_1") (pintype "passive"))
      (node (ref "DCDC-3.5V") (pin "INP#1") (pinfunction "VIN_INP#1") (pintype "bidirectional"))
      (node (ref "DCDC-3.5V") (pin "INP#2") (pinfunction "VIN_INP#2") (pintype "bidirectional"))
      (node (ref "IC4") (pin "3") (pinfunction "DVDD_3") (pintype "power_in"))
      (node (ref "J5") (pin "PWR") (pinfunction "PWR_PWR") (pintype "bidirectional"))
      (node (ref "R_CH1") (pin "1") (pinfunction "1_1") (pintype "passive"))
      (node (ref "R_CH2") (pin "1") (pinfunction "1_1") (pintype "passive"))
      (node (ref "R_CH3") (pin "1") (pinfunction "1_1") (pintype "passive"))
      (node (ref "R_CH4") (pin "1") (pinfunction "1_1") (pintype "passive"))
      (node (ref "SENSOR-MQ6") (pin "A1") (pinfunction "A1_A1") (pintype "bidirectional"))
      (node (ref "SENSOR-MQ6") (pin "A2") (pinfunction "A2_A2") (pintype "bidirectional"))
      (node (ref "SENSOR-MQ6") (pin "HA") (pinfunction "HA_HA") (pintype "bidirectional"))
      (node (ref "SENSOR-MQ7") (pin "A1") (pinfunction "A1_A1") (pintype "bidirectional"))
      (node (ref "SENSOR-MQ7") (pin "A2") (pinfunction "A2_A2") (pintype "bidirectional"))
      (node (ref "SENSOR-MQ7") (pin "HA") (pinfunction "HA_HA") (pintype "bidirectional"))
      (node (ref "SR_OUT1") (pin "1") (pinfunction "1_1") (pintype "passive"))
      (node (ref "SR_OUT2") (pin "1") (pinfunction "1_1") (pintype "passive"))
      (node (ref "SYS-C1") (pin "1") (pinfunction "1_1") (pintype "passive"))
      (node (ref "SYS-R1") (pin "1") (pinfunction "1_1") (pintype "passive"))
    )
    (net (code "3") (name "/GPIO11") (class "Default")
      (node (ref "IC1") (pin "P$67") (pinfunction "GPIO11_P$67") (pintype "power_in"))
    )
    (net (code "4") (name "/GPIO12") (class "Default")
      (node (ref "IC1") (pin "P$68") (pinfunction "GPIO12_P$68") (pintype "power_in"))
    )
    (net (code "5") (name "ACTLED") (class "Default")
      (node (ref "ETH-R4") (pin "1") (pinfunction "1_1") (pintype "passive"))
      (node (ref "U2") (pin "27") (pinfunction "ACTLED_27") (pintype "passive"))
    )
    (net (code "6") (name "ADE_APCF") (class "Default")
      (node (ref "IC4") (pin "1") (pinfunction "APCF_1") (pintype "output"))
      (node (ref "STM_CHIP") (pin "62") (pinfunction "PB9_62") (pintype "bidirectional"))
    )
    (net (code "7") (name "ADE_CS") (class "Default")
      (node (ref "IC4") (pin "21") (pinfunction "CS_21") (pintype "input"))
      (node (ref "STM_CHIP") (pin "58") (pinfunction "PB6_58") (pintype "bidirectional"))
    )
    (net (code "8") (name "ADE_IRQ") (class "Default")
      (node (ref "IC4") (pin "18") (pinfunction "IRQ_18") (pintype "output"))
      (node (ref "STM_CHIP") (pin "59") (pinfunction "PB7_59") (pintype "bidirectional"))
    )
    (net (code "9") (name "ADE_MISO") (class "Default")
      (node (ref "IC4") (pin "24") (pinfunction "DO_24") (pintype "output"))
      (node (ref "STM_CHIP") (pin "54") (pinfunction "PD2_54") (pintype "bidirectional"))
    )
    (net (code "10") (name "ADE_MOSI") (class "Default")
      (node (ref "IC4") (pin "22") (pinfunction "DI_22") (pintype "input"))
      (node (ref "STM_CHIP") (pin "57") (pinfunction "PB5_57") (pintype "bidirectional"))
    )
    (net (code "11") (name "ADE_SCK") (class "Default")
      (node (ref "IC4") (pin "23") (pinfunction "SCK_23") (pintype "input"))
      (node (ref "STM_CHIP") (pin "56") (pinfunction "PB4_56") (pintype "bidirectional"))
    )
    (net (code "12") (name "ADE_VARCF") (class "Default")
      (node (ref "IC4") (pin "17") (pinfunction "VARCF_17") (pintype "output"))
      (node (ref "STM_CHIP") (pin "61") (pinfunction "PB8_61") (pintype "bidirectional"))
    )
    (net (code "13") (name "AGND") (class "Default")
      (node (ref "ADE-C1") (pin "2") (pinfunction "2_2") (pintype "passive"))
      (node (ref "ADE-C10") (pin "2") (pinfunction "2_2") (pintype "passive"))
      (node (ref "ADE-C11") (pin "2") (pinfunction "2_2") (pintype "passive"))
      (node (ref "ADE-C12") (pin "2") (pinfunction "2_2") (pintype "passive"))
      (node (ref "ADE-C13") (pin "2") (pinfunction "2_2") (pintype "passive"))
      (node (ref "ADE-C14") (pin "2") (pinfunction "2_2") (pintype "passive"))
      (node (ref "ADE-C15") (pin "2") (pinfunction "2_2") (pintype "passive"))
      (node (ref "ADE-C16") (pin "2") (pinfunction "2_2") (pintype "passive"))
      (node (ref "ADE-C2") (pin "2") (pinfunction "2_2") (pintype "passive"))
      (node (ref "ADE-C7") (pin "2") (pinfunction "2_2") (pintype "passive"))
      (node (ref "ADE-C8") (pin "2") (pinfunction "2_2") (pintype "passive"))
      (node (ref "ADE-C9") (pin "2") (pinfunction "2_2") (pintype "passive"))
      (node (ref "ADE-R4") (pin "1") (pinfunction "1_1") (pintype "passive"))
      (node (ref "ADE-R5") (pin "1") (pinfunction "1_1") (pintype "passive"))
      (node (ref "ADE-R6") (pin "1") (pinfunction "1_1") (pintype "passive"))
      (node (ref "ETHERNET") (pin "4") (pinfunction "GND1_4") (pintype "bidirectional"))
      (node (ref "ETHERNET") (pin "5") (pinfunction "GND2_5") (pintype "bidirectional"))
      (node (ref "IC4") (pin "11") (pinfunction "AGND_11") (pintype "power_in"))
      (node (ref "STM-C9") (pin "2") (pinfunction "2_2") (pintype "passive"))
      (node (ref "STM_CHIP") (pin "12") (pinfunction "VSSA_12") (pintype "power_in"))
      (node (ref "SYS-C2") (pin "2") (pinfunction "2_2") (pintype "passive"))
      (node (ref "SYS-C4") (pin "2") (pinfunction "2_2") (pintype "passive"))
      (node (ref "SYS-L1") (pin "1") (pinfunction "1_1") (pintype "passive"))
    )
    (net (code "14") (name "CH1_A") (class "Default")
      (node (ref "JP1") (pin "2") (pinfunction "2_2") (pintype "passive"))
      (node (ref "OK2") (pin "8") (pinfunction "COL_8") (pintype "passive"))
    )
    (net (code "15") (name "CH1_B") (class "Default")
      (node (ref "JP1") (pin "1") (pinfunction "1_1") (pintype "passive"))
      (node (ref "OK2") (pin "7") (pinfunction "EMIT_7") (pintype "passive"))
    )
    (net (code "16") (name "CH1_IN") (class "Default")
      (node (ref "IC5") (pin "15") (pinfunction "QA_15") (pintype "tri_state"))
      (node (ref "OK2") (pin "2") (pinfunction "C_2") (pintype "passive"))
    )
    (net (code "17") (name "CH2_A") (class "Default")
      (node (ref "JP1") (pin "4") (pinfunction "4_4") (pintype "passive"))
      (node (ref "OK2") (pin "6") (pinfunction "COL_6") (pintype "passive"))
    )
    (net (code "18") (name "CH2_B") (class "Default")
      (node (ref "JP1") (pin "3") (pinfunction "3_3") (pintype "passive"))
      (node (ref "OK2") (pin "5") (pinfunction "EMIT_5") (pintype "passive"))
    )
    (net (code "19") (name "CH2_IN") (class "Default")
      (node (ref "IC5") (pin "1") (pinfunction "QB_1") (pintype "tri_state"))
      (node (ref "OK2") (pin "4") (pinfunction "C_4") (pintype "passive"))
    )
    (net (code "20") (name "CH3_A") (class "Default")
      (node (ref "JP1") (pin "6") (pinfunction "6_6") (pintype "passive"))
      (node (ref "OK1") (pin "8") (pinfunction "COL_8") (pintype "passive"))
    )
    (net (code "21") (name "CH3_B") (class "Default")
      (node (ref "JP1") (pin "5") (pinfunction "5_5") (pintype "passive"))
      (node (ref "OK1") (pin "7") (pinfunction "EMIT_7") (pintype "passive"))
    )
    (net (code "22") (name "CH3_IN") (class "Default")
      (node (ref "IC5") (pin "2") (pinfunction "QC_2") (pintype "tri_state"))
      (node (ref "OK1") (pin "2") (pinfunction "C_2") (pintype "passive"))
    )
    (net (code "23") (name "CH4_A") (class "Default")
      (node (ref "JP1") (pin "8") (pinfunction "8_8") (pintype "passive"))
      (node (ref "OK1") (pin "6") (pinfunction "COL_6") (pintype "passive"))
    )
    (net (code "24") (name "CH4_B") (class "Default")
      (node (ref "JP1") (pin "7") (pinfunction "7_7") (pintype "passive"))
      (node (ref "OK1") (pin "5") (pinfunction "EMIT_5") (pintype "passive"))
    )
    (net (code "25") (name "CH4_IN") (class "Default")
      (node (ref "IC5") (pin "3") (pinfunction "QD_3") (pintype "tri_state"))
      (node (ref "OK1") (pin "4") (pinfunction "C_4") (pintype "passive"))
    )
    (net (code "26") (name "DC_VOUT") (class "Default")
      (node (ref "DCDC-3.5V") (pin "OUTP#1") (pinfunction "VOUT_OUTP#1") (pintype "bidirectional"))
      (node (ref "DCDC-3.5V") (pin "OUTP#2") (pinfunction "VOUT_OUTP#2") (pintype "bidirectional"))
      (node (ref "PWR-SWT") (pin "2") (pinfunction "2_2") (pintype "passive"))
    )
    (net (code "27") (name "DGND") (class "Default")
      (node (ref "ADE-C3") (pin "2") (pinfunction "2_2") (pintype "passive"))
      (node (ref "ADE-C4") (pin "2") (pinfunction "2_2") (pintype "passive"))
      (node (ref "ADE-C5") (pin "-") (pinfunction "-_-") (pintype "passive"))
      (node (ref "ADE-C6") (pin "2") (pinfunction "2_2") (pintype "passive"))
      (node (ref "BAT1") (pin "2") (pinfunction "-_2") (pintype "power_in"))
      (node (ref "DCDC-3.5V") (pin "INM#1") (pinfunction "GNDI_INM#1") (pintype "bidirectional"))
      (node (ref "DCDC-3.5V") (pin "INM#2") (pinfunction "GNDI_INM#2") (pintype "bidirectional"))
      (node (ref "DCDC-3.5V") (pin "OUTM#1") (pinfunction "GNDO_OUTM#1") (pintype "bidirectional"))
      (node (ref "DCDC-3.5V") (pin "OUTM#2") (pinfunction "GNDO_OUTM#2") (pintype "bidirectional"))
      (node (ref "ESP-GND") (pin "1") (pinfunction "1_1") (pintype "passive"))
      (node (ref "ETH-C1") (pin "1") (pinfunction "1_1") (pintype "passive"))
      (node (ref "ETH-C3") (pin "1") (pinfunction "1_1") (pintype "passive"))
      (node (ref "IC1") (pin "P$17") (pinfunction "GND_P$17") (pintype "power_in"))
      (node (ref "IC1") (pin "P$18") (pinfunction "GND_P$18") (pintype "power_in"))
      (node (ref "IC1") (pin "P$29") (pinfunction "GND_P$29") (pintype "power_in"))
      (node (ref "IC1") (pin "P$39") (pinfunction "GND_P$39") (pintype "power_in"))
      (node (ref "IC1") (pin "P$45") (pinfunction "GND_P$45") (pintype "power_in"))
      (node (ref "IC1") (pin "P$46") (pinfunction "GND_P$46") (pintype "power_in"))
      (node (ref "IC1") (pin "P$53") (pinfunction "GND_P$53") (pintype "power_in"))
      (node (ref "IC1") (pin "P$54") (pinfunction "GND_P$54") (pintype "power_in"))
      (node (ref "IC1") (pin "P$58") (pinfunction "GND_P$58") (pintype "power_in"))
      (node (ref "IC1") (pin "P$59") (pinfunction "GND_P$59") (pintype "power_in"))
      (node (ref "IC1") (pin "P$61") (pinfunction "GND_P$61") (pintype "power_in"))
      (node (ref "IC1") (pin "P$62") (pinfunction "GND_P$62") (pintype "power_in"))
      (node (ref "IC1") (pin "P$63") (pinfunction "GND_P$63") (pintype "power_in"))
      (node (ref "IC1") (pin "P$64") (pinfunction "GND_P$64") (pintype "power_in"))
      (node (ref "IC1") (pin "P$65") (pinfunction "GND_P$65") (pintype "power_in"))
      (node (ref "IC2") (pin "13") (pinfunction "G_13") (pintype "input"))
      (node (ref "IC2") (pin "8") (pinfunction "GND_8") (pintype "power_in"))
      (node (ref "IC3") (pin "13") (pinfunction "G_13") (pintype "input"))
      (node (ref "IC3") (pin "8") (pinfunction "GND_8") (pintype "power_in"))
      (node (ref "IC4") (pin "2") (pinfunction "DGND_2") (pintype "power_in"))
      (node (ref "IC5") (pin "13") (pinfunction "G_13") (pintype "input"))
      (node (ref "IC5") (pin "8") (pinfunction "GND_8") (pintype "power_in"))
      (node (ref "J5") (pin "GND") (pinfunction "GND_GND") (pintype "bidirectional"))
      (node (ref "J5") (pin "GNDBREAK") (pinfunction "GNDBREAK_GNDBREAK") (pintype "bidirectional"))
      (node (ref "MQ6-R1") (pin "1") (pinfunction "1_1") (pintype "passive"))
      (node (ref "MQ7-R1") (pin "1") (pinfunction "1_1") (pintype "passive"))
      (node (ref "S1") (pin "3") (pinfunction "3_3") (pintype "passive"))
      (node (ref "S1") (pin "4") (pinfunction "4_4") (pintype "passive"))
      (node (ref "SENSOR-DHT") (pin "4") (pinfunction "4_4") (pintype "passive"))
      (node (ref "SENSOR-MQ6") (pin "HB") (pinfunction "HB_HB") (pintype "bidirectional"))
      (node (ref "SENSOR-MQ7") (pin "HB") (pinfunction "HB_HB") (pintype "bidirectional"))
      (node (ref "SIM900-C1") (pin "-") (pinfunction "-_-") (pintype "passive"))
      (node (ref "SIM900-C2") (pin "-") (pinfunction "-_-") (pintype "passive"))
      (node (ref "SIM900-C3") (pin "2") (pinfunction "2_2") (pintype "passive"))
      (node (ref "SIM900-C4") (pin "2") (pinfunction "2_2") (pintype "passive"))
      (node (ref "SIM900-C5") (pin "2") (pinfunction "2_2") (pintype "passive"))
      (node (ref "SIM900-R6") (pin "2") (pinfunction "2_2") (pintype "passive"))
      (node (ref "SIM900-R9") (pin "2") (pinfunction "2_2") (pintype "passive"))
      (node (ref "SIM900-T1") (pin "E") (pinfunction "E_E") (pintype "passive"))
      (node (ref "SIM900-T2") (pin "E") (pinfunction "E_E") (pintype "passive"))
      (node (ref "SIM900-T3") (pin "E") (pinfunction "E_E") (pintype "passive"))
      (node (ref "SIM900-T4") (pin "E") (pinfunction "E_E") (pintype "passive"))
      (node (ref "SIM_C1") (pin "1") (pinfunction "1_1") (pintype "passive"))
      (node (ref "SIM_C2") (pin "1") (pinfunction "1_1") (pintype "passive"))
      (node (ref "SR_OUT1") (pin "2") (pinfunction "2_2") (pintype "passive"))
      (node (ref "SR_OUT2") (pin "2") (pinfunction "2_2") (pintype "passive"))
      (node (ref "STM-C1") (pin "1") (pinfunction "1_1") (pintype "passive"))
      (node (ref "STM-C10") (pin "2") (pinfunction "2_2") (pintype "passive"))
      (node (ref "STM-C11") (pin "2") (pinfunction "2_2") (pintype "passive"))
      (node (ref "STM-C12") (pin "2") (pinfunction "2_2") (pintype "passive"))
      (node (ref "STM-C13") (pin "2") (pinfunction "2_2") (pintype "passive"))
      (node (ref "STM-C2") (pin "1") (pinfunction "1_1") (pintype "passive"))
      (node (ref "STM-C3") (pin "1") (pinfunction "1_1") (pintype "passive"))
      (node (ref "STM-C8") (pin "2") (pinfunction "2_2") (pintype "passive"))
      (node (ref "STM-SWD") (pin "3") (pinfunction "3_3") (pintype "passive"))
      (node (ref "STM-USART") (pin "4") (pinfunction "4_4") (pintype "passive"))
      (node (ref "STM_CHIP") (pin "18") (pinfunction "VSS_4_18") (pintype "power_in"))
      (node (ref "STM_CHIP") (pin "31") (pinfunction "VSS_1_31") (pintype "power_in"))
      (node (ref "STM_CHIP") (pin "47") (pinfunction "VSS_2_47") (pintype "power_in"))
      (node (ref "STM_CHIP") (pin "63") (pinfunction "VSS_3_63") (pintype "power_in"))
      (node (ref "SYS-C1") (pin "2") (pinfunction "2_2") (pintype "passive"))
      (node (ref "SYS-C3") (pin "2") (pinfunction "2_2") (pintype "passive"))
      (node (ref "SYS-L1") (pin "2") (pinfunction "2_2") (pintype "passive"))
      (node (ref "U$4") (pin "LCD_GND") (pinfunction "LCD_GND_LCD_GND") (pintype "passive"))
      (node (ref "U$6") (pin "1") (pinfunction "2_1") (pintype "passive"))
      (node (ref "U$7") (pin "P$1") (pinfunction "GND_P$1") (pintype "bidirectional"))
      (node (ref "U$7") (pin "P$2") (pinfunction "GND_P$2") (pintype "bidirectional"))
      (node (ref "U$8") (pin "SHIELD_GND$1") (pinfunction "GND$1_SHIELD_GND$1") (pintype "bidirectional"))
      (node (ref "U$8") (pin "SHIELD_GND$2") (pinfunction "GND$2_SHIELD_GND$2") (pintype "bidirectional"))
      (node (ref "U$8") (pin "SIM_GND") (pinfunction "SIM_GND_SIM_GND") (pintype "bidirectional"))
      (node (ref "U2") (pin "14") (pinfunction "AGND_14") (pintype "passive"))
      (node (ref "U2") (pin "16") (pinfunction "AGND_16") (pintype "passive"))
      (node (ref "U2") (pin "19") (pinfunction "AGND_19") (pintype "passive"))
      (node (ref "U2") (pin "29") (pinfunction "GND_29") (pintype "passive"))
      (node (ref "U2") (pin "3") (pinfunction "AGND_3") (pintype "passive"))
      (node (ref "U2") (pin "48") (pinfunction "AGND_48") (pintype "passive"))
      (node (ref "U2") (pin "9") (pinfunction "AGND_9") (pintype "passive"))
      (node (ref "W5500-C1") (pin "2") (pinfunction "2_2") (pintype "passive"))
      (node (ref "W5500-C10") (pin "2") (pinfunction "2_2") (pintype "passive"))
      (node (ref "W5500-C11") (pin "2") (pinfunction "2_2") (pintype "passive"))
      (node (ref "W5500-C12") (pin "-") (pinfunction "-_-") (pintype "passive"))
      (node (ref "W5500-C13") (pin "-") (pinfunction "-_-") (pintype "passive"))
      (node (ref "W5500-C2") (pin "2") (pinfunction "2_2") (pintype "passive"))
      (node (ref "W5500-C3") (pin "2") (pinfunction "2_2") (pintype "passive"))
      (node (ref "W5500-C4") (pin "2") (pinfunction "2_2") (pintype "passive"))
      (node (ref "W5500-C5") (pin "2") (pinfunction "2_2") (pintype "passive"))
      (node (ref "W5500-C6") (pin "2") (pinfunction "2_2") (pintype "passive"))
      (node (ref "W5500-C7") (pin "2") (pinfunction "2_2") (pintype "passive"))
      (node (ref "W5500-C8") (pin "2") (pinfunction "2_2") (pintype "passive"))
      (node (ref "W5500-C9") (pin "2") (pinfunction "2_2") (pintype "passive"))
      (node (ref "W5500-R11") (pin "1") (pinfunction "1_1") (pintype "passive"))
      (node (ref "W5500-R12") (pin "1") (pinfunction "1_1") (pintype "passive"))
      (node (ref "W5500-R4") (pin "2") (pinfunction "2_2") (pintype "passive"))
      (node (ref "W5500-R5") (pin "2") (pinfunction "2_2") (pintype "passive"))
      (node (ref "W5500-R6") (pin "2") (pinfunction "2_2") (pintype "passive"))
      (node (ref "W5500-R7") (pin "2") (pinfunction "2_2") (pintype "passive"))
      (node (ref "W5500-R8") (pin "2") (pinfunction "2_2") (pintype "passive"))
    )
    (net (code "28") (name "DHT_DATA") (class "Default")
      (node (ref "DHT-R1") (pin "2") (pinfunction "2_2") (pintype "passive"))
      (node (ref "SENSOR-DHT") (pin "2") (pinfunction "2_2") (pintype "passive"))
      (node (ref "STM_CHIP") (pin "15") (pinfunction "PA1_15") (pintype "bidirectional"))
    )
    (net (code "29") (name "ESP_GPIO0") (class "Default")
      (node (ref "ESP-GPIO0") (pin "2") (pinfunction "2_2") (pintype "passive"))
      (node (ref "U$5") (pin "GPIO00") (pinfunction "GPIO0_GPIO00") (pintype "bidirectional"))
    )
    (net (code "30") (name "ESP_RX") (class "Default")
      (node (ref "ESP-UART-A") (pin "2") (pinfunction "2_2") (pintype "passive"))
      (node (ref "JP_ESP_RX") (pin "1") (pinfunction "1_1") (pintype "passive"))
      (node (ref "U$5") (pin "RXD") (pinfunction "RXD_RXD") (pintype "bidirectional"))
    )
    (net (code "31") (name "ESP_TX") (class "Default")
      (node (ref "ESP-UART-A") (pin "3") (pinfunction "3_3") (pintype "passive"))
      (node (ref "JP_ESP_TX") (pin "1") (pinfunction "1_1") (pintype "passive"))
      (node (ref "U$5") (pin "TXD") (pinfunction "TXD_TXD") (pintype "bidirectional"))
    )
    (net (code "32") (name "ETH_CS") (class "Default")
      (node (ref "STM_CHIP") (pin "33") (pinfunction "PB12_33") (pintype "bidirectional"))
      (node (ref "U2") (pin "32") (pinfunction "SCS_N_32") (pintype "passive"))
      (node (ref "W5500-R13") (pin "1") (pinfunction "1_1") (pintype "passive"))
    )
    (net (code "33") (name "ETH_MISO") (class "Default")
      (node (ref "STM_CHIP") (pin "35") (pinfunction "PB14_35") (pintype "bidirectional"))
      (node (ref "U2") (pin "34") (pinfunction "MISO_34") (pintype "passive"))
    )
    (net (code "34") (name "ETH_MOSI") (class "Default")
      (node (ref "STM_CHIP") (pin "36") (pinfunction "PB15_36") (pintype "bidirectional"))
      (node (ref "U2") (pin "35") (pinfunction "MOSI_35") (pintype "passive"))
    )
    (net (code "35") (name "ETH_RSTN") (class "Default")
      (node (ref "STM_CHIP") (pin "37") (pinfunction "PC6_37") (pintype "bidirectional"))
      (node (ref "U2") (pin "37") (pinfunction "RST_N_37") (pintype "passive"))
      (node (ref "W5500-R9") (pin "1") (pinfunction "1_1") (pintype "passive"))
    )
    (net (code "36") (name "ETH_SCK") (class "Default")
      (node (ref "STM_CHIP") (pin "34") (pinfunction "PB13_34") (pintype "bidirectional"))
      (node (ref "U2") (pin "33") (pinfunction "SCLK_33") (pintype "passive"))
    )
    (net (code "37") (name "F_CS") (class "Default")
      (node (ref "STM_CHIP") (pin "29") (pinfunction "PB10_29") (pintype "bidirectional"))
      (node (ref "U$4") (pin "F_CS") (pinfunction "F_CS_F_CS") (pintype "passive"))
    )
    (net (code "38") (name "GESP") (class "Default")
      (node (ref "ESP-C1") (pin "2") (pinfunction "2_2") (pintype "passive"))
      (node (ref "ESP-GND") (pin "2") (pinfunction "2_2") (pintype "passive"))
      (node (ref "ESP-GPIO0") (pin "3") (pinfunction "3_3") (pintype "passive"))
      (node (ref "U$5") (pin "GND") (pinfunction "GND_GND") (pintype "bidirectional"))
      (node (ref "U$5") (pin "GPIO15") (pinfunction "GPIO15_GPIO15") (pintype "bidirectional"))
    )
    (net (code "39") (name "GEXT") (class "Default")
      (node (ref "ESP-GND") (pin "3") (pinfunction "3_3") (pintype "passive"))
      (node (ref "ESP-UART-A") (pin "4") (pinfunction "4_4") (pintype "passive"))
    )
    (net (code "40") (name "LCD_CS") (class "Default")
      (node (ref "STM_CHIP") (pin "20") (pinfunction "PA4_20") (pintype "bidirectional"))
      (node (ref "U$4") (pin "LCD_CS") (pinfunction "LCD_CS_LCD_CS") (pintype "passive"))
    )
    (net (code "41") (name "LCD_D{slash}C") (class "Default")
      (node (ref "STM_CHIP") (pin "24") (pinfunction "PC4_24") (pintype "bidirectional"))
      (node (ref "U$4") (pin "LCD_D/C") (pinfunction "LCD_D/C_LCD_D/C") (pintype "passive"))
    )
    (net (code "42") (name "LCD_LED") (class "Default")
      (node (ref "LCD-R1") (pin "1") (pinfunction "1_1") (pintype "passive"))
      (node (ref "U$4") (pin "LCD_LED") (pinfunction "LCD_LED_LCD_LED") (pintype "passive"))
    )
    (net (code "43") (name "LCD_MISO") (class "Default")
      (node (ref "STM_CHIP") (pin "22") (pinfunction "PA6_22") (pintype "bidirectional"))
      (node (ref "U$4") (pin "LCD_MISO") (pinfunction "LCD_MISO_LCD_MISO") (pintype "passive"))
      (node (ref "U$4") (pin "SD_MISO") (pinfunction "SD_MISO_SD_MISO") (pintype "passive"))
    )
    (net (code "44") (name "LCD_MOSI") (class "Default")
      (node (ref "STM_CHIP") (pin "23") (pinfunction "PA7_23") (pintype "bidirectional"))
      (node (ref "U$4") (pin "LCD_MOSI") (pinfunction "LCD_MOSI_LCD_MOSI") (pintype "passive"))
      (node (ref "U$4") (pin "SD_MOSI") (pinfunction "SD_MOSI_SD_MOSI") (pintype "passive"))
    )
    (net (code "45") (name "LCD_RESET") (class "Default")
      (node (ref "STM_CHIP") (pin "25") (pinfunction "PC5_25") (pintype "bidirectional"))
      (node (ref "U$4") (pin "LCD_RESET") (pinfunction "LCD_RESET_LCD_RESET") (pintype "passive"))
    )
    (net (code "46") (name "LCD_SCK") (class "Default")
      (node (ref "STM_CHIP") (pin "21") (pinfunction "PA5_21") (pintype "bidirectional"))
      (node (ref "U$4") (pin "LCD_SCK") (pinfunction "LCD_SCK_LCD_SCK") (pintype "passive"))
      (node (ref "U$4") (pin "SD_SCK") (pinfunction "SD_SCK_SD_SCK") (pintype "passive"))
    )
    (net (code "47") (name "LINKLED") (class "Default")
      (node (ref "ETH-R5") (pin "1") (pinfunction "1_1") (pintype "passive"))
      (node (ref "U2") (pin "25") (pinfunction "LINKLED_25") (pintype "passive"))
    )
    (net (code "48") (name "MQ6_DATA") (class "Default")
      (node (ref "SENSOR-MQ7") (pin "B1") (pinfunction "B1_B1") (pintype "bidirectional"))
      (node (ref "STM_CHIP") (pin "26") (pinfunction "PB0_26") (pintype "bidirectional"))
    )
    (net (code "49") (name "MQ7_DATA") (class "Default")
      (node (ref "SENSOR-MQ6") (pin "B1") (pinfunction "B1_B1") (pintype "bidirectional"))
      (node (ref "STM_CHIP") (pin "27") (pinfunction "PB1_27") (pintype "bidirectional"))
    )
    (net (code "50") (name "Net-(ADE-R1-Pad1)") (class "Default")
      (node (ref "ADE-R1") (pin "1") (pinfunction "1_1") (pintype "passive"))
      (node (ref "RTO1") (pin "2") (pinfunction "2_2") (pintype "passive"))
      (node (ref "U$9") (pin "OA") (pinfunction "OA_OA") (pintype "bidirectional"))
    )
    (net (code "51") (name "Net-(ADE-R2-Pad1)") (class "Default")
      (node (ref "ADE-R2") (pin "1") (pinfunction "1_1") (pintype "passive"))
      (node (ref "RTO2") (pin "2") (pinfunction "2_2") (pintype "passive"))
      (node (ref "U$10") (pin "OA") (pinfunction "OA_OA") (pintype "bidirectional"))
    )
    (net (code "52") (name "Net-(ADE-R3-Pad1)") (class "Default")
      (node (ref "ADE-R3") (pin "1") (pinfunction "1_1") (pintype "passive"))
      (node (ref "RTO3") (pin "2") (pinfunction "2_2") (pintype "passive"))
      (node (ref "U$11") (pin "OA") (pinfunction "OA_OA") (pintype "bidirectional"))
    )
    (net (code "53") (name "Net-(ADE-R7-Pad1)") (class "Default")
      (node (ref "ADE-R7") (pin "1") (pinfunction "1_1") (pintype "passive"))
      (node (ref "RTO1") (pin "1") (pinfunction "1_1") (pintype "passive"))
      (node (ref "RTO2") (pin "1") (pinfunction "1_1") (pintype "passive"))
      (node (ref "RTO3") (pin "1") (pinfunction "1_1") (pintype "passive"))
      (node (ref "U$10") (pin "OB") (pinfunction "OB_OB") (pintype "bidirectional"))
      (node (ref "U$11") (pin "OB") (pinfunction "OB_OB") (pintype "bidirectional"))
      (node (ref "U$9") (pin "OB") (pinfunction "OB_OB") (pintype "bidirectional"))
    )
    (net (code "54") (name "Net-(ADE-R8-Pad2)") (class "Default")
      (node (ref "ADE-R8") (pin "2") (pinfunction "2_2") (pintype "passive"))
      (node (ref "ADE-R9") (pin "1") (pinfunction "1_1") (pintype "passive"))
      (node (ref "JP2") (pin "SLEEVE") (pinfunction "SLEEVE_SLEEVE") (pintype "bidirectional"))
    )
    (net (code "55") (name "Net-(ADE-R11-Pad2)") (class "Default")
      (node (ref "ADE-R11") (pin "2") (pinfunction "2_2") (pintype "passive"))
      (node (ref "ADE-R12") (pin "1") (pinfunction "1_1") (pintype "passive"))
      (node (ref "JP3") (pin "SLEEVE") (pinfunction "SLEEVE_SLEEVE") (pintype "bidirectional"))
    )
    (net (code "56") (name "Net-(ADE-R14-Pad2)") (class "Default")
      (node (ref "ADE-R14") (pin "2") (pinfunction "2_2") (pintype "passive"))
      (node (ref "ADE-R15") (pin "1") (pinfunction "1_1") (pintype "passive"))
      (node (ref "JP4") (pin "SLEEVE") (pinfunction "SLEEVE_SLEEVE") (pintype "bidirectional"))
    )
    (net (code "57") (name "Net-(ETHERNET-LED1_K)") (class "Default")
      (node (ref "ETH-R4") (pin "2") (pinfunction "2_2") (pintype "passive"))
      (node (ref "ETHERNET") (pin "10") (pinfunction "LED1_K_10") (pintype "bidirectional"))
    )
    (net (code "58") (name "Net-(ETHERNET-LED2_K)") (class "Default")
      (node (ref "ETH-R5") (pin "2") (pinfunction "2_2") (pintype "passive"))
      (node (ref "ETHERNET") (pin "11") (pinfunction "LED2_K_11") (pintype "bidirectional"))
    )
    (net (code "59") (name "Net-(ETHERNET-RCT)") (class "Default")
      (node (ref "ETH-C3") (pin "2") (pinfunction "2_2") (pintype "passive"))
      (node (ref "ETH-R6") (pin "1") (pinfunction "1_1") (pintype "passive"))
      (node (ref "ETH-R7") (pin "2") (pinfunction "2_2") (pintype "passive"))
      (node (ref "ETHERNET") (pin "6") (pinfunction "RCT_6") (pintype "bidirectional"))
    )
    (net (code "60") (name "Net-(ETHERNET-RX+)") (class "Default")
      (node (ref "ETH-C2") (pin "1") (pinfunction "1_1") (pintype "passive"))
      (node (ref "ETHERNET") (pin "7") (pinfunction "RX+_7") (pintype "bidirectional"))
    )
    (net (code "61") (name "Net-(ETHERNET-RX-)") (class "Default")
      (node (ref "ETH-C4") (pin "1") (pinfunction "1_1") (pintype "passive"))
      (node (ref "ETHERNET") (pin "8") (pinfunction "RX-_8") (pintype "bidirectional"))
    )
    (net (code "62") (name "Net-(ETHERNET-TCT)") (class "Default")
      (node (ref "ETH-C1") (pin "2") (pinfunction "2_2") (pintype "passive"))
      (node (ref "ETH-R3") (pin "1") (pinfunction "1_1") (pintype "passive"))
      (node (ref "ETHERNET") (pin "3") (pinfunction "TCT_3") (pintype "bidirectional"))
    )
    (net (code "63") (name "Net-(IC1-RF_ANT)") (class "Default")
      (node (ref "IC1") (pin "P$60") (pinfunction "RF_ANT_P$60") (pintype "bidirectional"))
      (node (ref "U$7") (pin "P$3") (pinfunction "SIGNAL_P$3") (pintype "bidirectional"))
    )
    (net (code "64") (name "Net-(IC1-SIM_CLK)") (class "Default")
      (node (ref "IC1") (pin "P$32") (pinfunction "SIM_CLK_P$32") (pintype "bidirectional"))
      (node (ref "SIM900-R2") (pin "1") (pinfunction "1_1") (pintype "passive"))
    )
    (net (code "65") (name "Net-(IC1-SIM_DATA)") (class "Default")
      (node (ref "IC1") (pin "P$31") (pinfunction "SIM_DATA_P$31") (pintype "bidirectional"))
      (node (ref "SIM900-R3") (pin "1") (pinfunction "1_1") (pintype "passive"))
    )
    (net (code "66") (name "Net-(IC1-SIM_RST)") (class "Default")
      (node (ref "IC1") (pin "P$33") (pinfunction "SIM_RST_P$33") (pintype "bidirectional"))
      (node (ref "SIM900-R1") (pin "1") (pinfunction "1_1") (pintype "passive"))
    )
    (net (code "67") (name "Net-(IC1-VBAT1)") (class "Default")
      (node (ref "IC1") (pin "P$55") (pinfunction "VBAT1_P$55") (pintype "power_in"))
      (node (ref "IC1") (pin "P$56") (pinfunction "VBAT2_P$56") (pintype "power_in"))
      (node (ref "IC1") (pin "P$57") (pinfunction "VBAT3_P$57") (pintype "power_in"))
      (node (ref "SIM900-C1") (pin "+") (pinfunction "+_+") (pintype "passive"))
      (node (ref "SIM900-C2") (pin "+") (pinfunction "+_+") (pintype "passive"))
      (node (ref "SYS-L2") (pin "1") (pinfunction "1_1") (pintype "passive"))
    )
    (net (code "68") (name "Net-(IC1-VRTC)") (class "Default")
      (node (ref "IC1") (pin "P$26") (pinfunction "VRTC_P$26") (pintype "power_in"))
      (node (ref "SIM900-C3") (pin "1") (pinfunction "1_1") (pintype "passive"))
    )
    (net (code "69") (name "Net-(IC4A-CLKIN)") (class "Default")
      (node (ref "ADE-C3") (pin "1") (pinfunction "1_1") (pintype "passive"))
      (node (ref "ADE-XTAL") (pin "1") (pinfunction "1_1") (pintype "passive"))
      (node (ref "IC4") (pin "19") (pinfunction "CLKIN_19") (pintype "input"))
    )
    (net (code "70") (name "Net-(IC4A-CLKOUT)") (class "Default")
      (node (ref "ADE-C4") (pin "1") (pinfunction "1_1") (pintype "passive"))
      (node (ref "ADE-XTAL") (pin "2") (pinfunction "2_2") (pintype "passive"))
      (node (ref "IC4") (pin "20") (pinfunction "CLKOUT_20") (pintype "output"))
    )
    (net (code "71") (name "Net-(IC4C-IN)") (class "Default")
      (node (ref "ADE-C12") (pin "1") (pinfunction "1_1") (pintype "passive"))
      (node (ref "ADE-R10") (pin "2") (pinfunction "2_2") (pintype "passive"))
      (node (ref "IC4") (pin "6") (pinfunction "IN_6") (pintype "input"))
    )
    (net (code "72") (name "Net-(IC4C-IP)") (class "Default")
      (node (ref "ADE-C11") (pin "1") (pinfunction "1_1") (pintype "passive"))
      (node (ref "ADE-R9") (pin "2") (pinfunction "2_2") (pintype "passive"))
      (node (ref "IC4") (pin "5") (pinfunction "IP_5") (pintype "input"))
    )
    (net (code "73") (name "Net-(IC4D-IN)") (class "Default")
      (node (ref "ADE-C14") (pin "1") (pinfunction "1_1") (pintype "passive"))
      (node (ref "ADE-R13") (pin "2") (pinfunction "2_2") (pintype "passive"))
      (node (ref "IC4") (pin "8") (pinfunction "IN_8") (pintype "input"))
    )
    (net (code "74") (name "Net-(IC4D-IP)") (class "Default")
      (node (ref "ADE-C13") (pin "1") (pinfunction "1_1") (pintype "passive"))
      (node (ref "ADE-R12") (pin "2") (pinfunction "2_2") (pintype "passive"))
      (node (ref "IC4") (pin "7") (pinfunction "IP_7") (pintype "input"))
    )
    (net (code "75") (name "Net-(IC4E-IN)") (class "Default")
      (node (ref "ADE-C16") (pin "1") (pinfunction "1_1") (pintype "passive"))
      (node (ref "ADE-R16") (pin "2") (pinfunction "2_2") (pintype "passive"))
      (node (ref "IC4") (pin "10") (pinfunction "IN_10") (pintype "input"))
    )
    (net (code "76") (name "Net-(IC4E-IP)") (class "Default")
      (node (ref "ADE-C15") (pin "1") (pinfunction "1_1") (pintype "passive"))
      (node (ref "ADE-R15") (pin "2") (pinfunction "2_2") (pintype "passive"))
      (node (ref "IC4") (pin "9") (pinfunction "IP_9") (pintype "input"))
    )
    (net (code "77") (name "Net-(IC4F-REF)") (class "Default")
      (node (ref "ADE-C1") (pin "1") (pinfunction "1_1") (pintype "passive"))
      (node (ref "ADE-C2") (pin "1") (pinfunction "1_1") (pintype "passive"))
      (node (ref "IC4") (pin "12") (pinfunction "REF_12") (pintype "bidirectional"))
    )
    (net (code "78") (name "Net-(IC4G-VAP)") (class "Default")
      (node (ref "ADE-C7") (pin "1") (pinfunction "1_1") (pintype "passive"))
      (node (ref "ADE-R1") (pin "2") (pinfunction "2_2") (pintype "passive"))
      (node (ref "ADE-R4") (pin "2") (pinfunction "2_2") (pintype "passive"))
      (node (ref "IC4") (pin "16") (pinfunction "VAP_16") (pintype "input"))
    )
    (net (code "79") (name "Net-(IC4G-VBP)") (class "Default")
      (node (ref "ADE-C8") (pin "1") (pinfunction "1_1") (pintype "passive"))
      (node (ref "ADE-R2") (pin "2") (pinfunction "2_2") (pintype "passive"))
      (node (ref "ADE-R5") (pin "2") (pinfunction "2_2") (pintype "passive"))
      (node (ref "IC4") (pin "15") (pinfunction "VBP_15") (pintype "input"))
    )
    (net (code "80") (name "Net-(IC4G-VCP)") (class "Default")
      (node (ref "ADE-C9") (pin "1") (pinfunction "1_1") (pintype "passive"))
      (node (ref "ADE-R3") (pin "2") (pinfunction "2_2") (pintype "passive"))
      (node (ref "ADE-R6") (pin "2") (pinfunction "2_2") (pintype "passive"))
      (node (ref "IC4") (pin "14") (pinfunction "VCP_14") (pintype "input"))
    )
    (net (code "81") (name "Net-(IC4G-VN)") (class "Default")
      (node (ref "ADE-C10") (pin "1") (pinfunction "1_1") (pintype "passive"))
      (node (ref "ADE-R7") (pin "2") (pinfunction "2_2") (pintype "passive"))
      (node (ref "IC4") (pin "13") (pinfunction "VN_13") (pintype "input"))
    )
    (net (code "82") (name "Net-(JP2-LEFT)") (class "Default")
      (node (ref "ADE-R10") (pin "1") (pinfunction "1_1") (pintype "passive"))
      (node (ref "ADE-R8") (pin "1") (pinfunction "1_1") (pintype "passive"))
      (node (ref "JP2") (pin "RING") (pinfunction "RIGHT_RING") (pintype "bidirectional"))
      (node (ref "JP2") (pin "TIP") (pinfunction "LEFT_TIP") (pintype "bidirectional"))
    )
    (net (code "83") (name "Net-(JP3-LEFT)") (class "Default")
      (node (ref "ADE-R11") (pin "1") (pinfunction "1_1") (pintype "passive"))
      (node (ref "ADE-R13") (pin "1") (pinfunction "1_1") (pintype "passive"))
      (node (ref "JP3") (pin "RING") (pinfunction "RIGHT_RING") (pintype "bidirectional"))
      (node (ref "JP3") (pin "TIP") (pinfunction "LEFT_TIP") (pintype "bidirectional"))
    )
    (net (code "84") (name "Net-(JP4-LEFT)") (class "Default")
      (node (ref "ADE-R14") (pin "1") (pinfunction "1_1") (pintype "passive"))
      (node (ref "ADE-R16") (pin "1") (pinfunction "1_1") (pintype "passive"))
      (node (ref "JP4") (pin "RING") (pinfunction "RIGHT_RING") (pintype "bidirectional"))
      (node (ref "JP4") (pin "TIP") (pinfunction "LEFT_TIP") (pintype "bidirectional"))
    )
    (net (code "85") (name "Net-(LED1-PadA)") (class "Default")
      (node (ref "LED1") (pin "A") (pinfunction "A_A") (pintype "passive"))
      (node (ref "R1") (pin "2") (pinfunction "2_2") (pintype "passive"))
    )
    (net (code "86") (name "Net-(MQ6-R1-Pad2)") (class "Default")
      (node (ref "MQ6-R1") (pin "2") (pinfunction "2_2") (pintype "passive"))
      (node (ref "SENSOR-MQ6") (pin "B2") (pinfunction "B2_B2") (pintype "bidirectional"))
    )
    (net (code "87") (name "Net-(MQ7-R1-Pad2)") (class "Default")
      (node (ref "MQ7-R1") (pin "2") (pinfunction "2_2") (pintype "passive"))
      (node (ref "SENSOR-MQ7") (pin "B2") (pinfunction "B2_B2") (pintype "bidirectional"))
    )
    (net (code "88") (name "Net-(OK1A-A)") (class "Default")
      (node (ref "OK1") (pin "1") (pinfunction "A_1") (pintype "passive"))
      (node (ref "R_CH3") (pin "2") (pinfunction "2_2") (pintype "passive"))
    )
    (net (code "89") (name "Net-(OK1B-A)") (class "Default")
      (node (ref "OK1") (pin "3") (pinfunction "A_3") (pintype "passive"))
      (node (ref "R_CH4") (pin "2") (pinfunction "2_2") (pintype "passive"))
    )
    (net (code "90") (name "Net-(OK2A-A)") (class "Default")
      (node (ref "OK2") (pin "1") (pinfunction "A_1") (pintype "passive"))
      (node (ref "R_CH1") (pin "2") (pinfunction "2_2") (pintype "passive"))
    )
    (net (code "91") (name "Net-(OK2B-A)") (class "Default")
      (node (ref "OK2") (pin "3") (pinfunction "A_3") (pintype "passive"))
      (node (ref "R_CH2") (pin "2") (pinfunction "2_2") (pintype "passive"))
    )
    (net (code "92") (name "Net-(RT1-Pad2)") (class "Default")
      (node (ref "RT1") (pin "2") (pinfunction "2_2") (pintype "passive"))
      (node (ref "U$9") (pin "IA") (pinfunction "IA_IA") (pintype "bidirectional"))
    )
    (net (code "93") (name "Net-(RT2-Pad2)") (class "Default")
      (node (ref "RT2") (pin "2") (pinfunction "2_2") (pintype "passive"))
      (node (ref "U$10") (pin "IA") (pinfunction "IA_IA") (pintype "bidirectional"))
    )
    (net (code "94") (name "Net-(RT3-Pad2)") (class "Default")
      (node (ref "RT3") (pin "2") (pinfunction "2_2") (pintype "passive"))
      (node (ref "U$11") (pin "IA") (pinfunction "IA_IA") (pintype "bidirectional"))
    )
    (net (code "95") (name "Net-(SIM900-LED1-PadA)") (class "Default")
      (node (ref "SIM900-LED1") (pin "A") (pinfunction "A_A") (pintype "passive"))
      (node (ref "SIM900-R4") (pin "1") (pinfunction "1_1") (pintype "passive"))
    )
    (net (code "96") (name "Net-(SIM900-LED1-PadC)") (class "Default")
      (node (ref "SIM900-LED1") (pin "C") (pinfunction "C_C") (pintype "passive"))
      (node (ref "SIM900-T1") (pin "C") (pinfunction "C_C") (pintype "passive"))
    )
    (net (code "97") (name "Net-(SIM900-LED2-PadA)") (class "Default")
      (node (ref "SIM900-LED2") (pin "A") (pinfunction "A_A") (pintype "passive"))
      (node (ref "SIM900-R7") (pin "1") (pinfunction "1_1") (pintype "passive"))
    )
    (net (code "98") (name "Net-(SIM900-LED2-PadC)") (class "Default")
      (node (ref "SIM900-LED2") (pin "C") (pinfunction "C_C") (pintype "passive"))
      (node (ref "SIM900-T2") (pin "C") (pinfunction "C_C") (pintype "passive"))
    )
    (net (code "99") (name "Net-(SIM900-R5-Pad1)") (class "Default")
      (node (ref "SIM900-R5") (pin "1") (pinfunction "1_1") (pintype "passive"))
      (node (ref "SIM900-R6") (pin "1") (pinfunction "1_1") (pintype "passive"))
      (node (ref "SIM900-T1") (pin "B") (pinfunction "B_B") (pintype "passive"))
    )
    (net (code "100") (name "Net-(SIM900-R8-Pad1)") (class "Default")
      (node (ref "SIM900-R8") (pin "1") (pinfunction "1_1") (pintype "passive"))
      (node (ref "SIM900-R9") (pin "1") (pinfunction "1_1") (pintype "passive"))
      (node (ref "SIM900-T2") (pin "B") (pinfunction "B_B") (pintype "passive"))
    )
    (net (code "101") (name "Net-(SIM900-R10-Pad2)") (class "Default")
      (node (ref "SIM900-R10") (pin "2") (pinfunction "2_2") (pintype "passive"))
      (node (ref "SIM900-T3") (pin "B") (pinfunction "B_B") (pintype "passive"))
    )
    (net (code "102") (name "Net-(SIM900-R11-Pad2)") (class "Default")
      (node (ref "SIM900-R11") (pin "2") (pinfunction "2_2") (pintype "passive"))
      (node (ref "SIM900-T4") (pin "B") (pinfunction "B_B") (pintype "passive"))
    )
    (net (code "103") (name "Net-(STM_CHIP-PA2)") (class "Default")
      (node (ref "JP_ESP_RX") (pin "2") (pinfunction "2_2") (pintype "passive"))
      (node (ref "STM_CHIP") (pin "16") (pinfunction "PA2_16") (pintype "bidirectional"))
    )
    (net (code "104") (name "Net-(STM_CHIP-PA3)") (class "Default")
      (node (ref "JP_ESP_TX") (pin "2") (pinfunction "2_2") (pintype "passive"))
      (node (ref "STM_CHIP") (pin "17") (pinfunction "PA3_17") (pintype "bidirectional"))
    )
    (net (code "105") (name "Net-(STM_CHIP-PC8)") (class "Default")
      (node (ref "LED1") (pin "C") (pinfunction "C_C") (pintype "passive"))
      (node (ref "STM_CHIP") (pin "39") (pinfunction "PC8_39") (pintype "bidirectional"))
    )
    (net (code "106") (name "Net-(STM_CHIP-PC14-OSC32_IN)") (class "Default")
      (node (ref "STM-C2") (pin "2") (pinfunction "2_2") (pintype "passive"))
      (node (ref "STM-XTAL") (pin "2") (pinfunction "2_2") (pintype "passive"))
      (node (ref "STM_CHIP") (pin "3") (pinfunction "PC14-OSC32_IN_3") (pintype "bidirectional"))
    )
    (net (code "107") (name "Net-(STM_CHIP-PC15-OSC32_OUT)") (class "Default")
      (node (ref "STM-C3") (pin "2") (pinfunction "2_2") (pintype "passive"))
      (node (ref "STM-XTAL") (pin "1") (pinfunction "1_1") (pintype "passive"))
      (node (ref "STM_CHIP") (pin "4") (pinfunction "PC15-OSC32_OUT_4") (pintype "bidirectional"))
    )
    (net (code "108") (name "Net-(U$12-P$1)") (class "Default")
      (node (ref "RT1") (pin "1") (pinfunction "1_1") (pintype "passive"))
      (node (ref "U$12") (pin "P1") (pinfunction "P$1_P1") (pintype "bidirectional"))
    )
    (net (code "109") (name "Net-(U$12-P$2)") (class "Default")
      (node (ref "RT2") (pin "1") (pinfunction "1_1") (pintype "passive"))
      (node (ref "U$12") (pin "P2") (pinfunction "P$2_P2") (pintype "bidirectional"))
    )
    (net (code "110") (name "Net-(U$12-P$3)") (class "Default")
      (node (ref "RT3") (pin "1") (pinfunction "1_1") (pintype "passive"))
      (node (ref "U$12") (pin "P3") (pinfunction "P$3_P3") (pintype "bidirectional"))
    )
    (net (code "111") (name "Net-(U$12-P$4)") (class "Default")
      (node (ref "U$10") (pin "IB") (pinfunction "IB_IB") (pintype "bidirectional"))
      (node (ref "U$11") (pin "IB") (pinfunction "IB_IB") (pintype "bidirectional"))
      (node (ref "U$12") (pin "P4") (pinfunction "P$4_P4") (pintype "bidirectional"))
      (node (ref "U$9") (pin "IB") (pinfunction "IB_IB") (pintype "bidirectional"))
    )
    (net (code "112") (name "Net-(U2-1V2O)") (class "Default")
      (node (ref "U2") (pin "22") (pinfunction "1V2O_22") (pintype "passive"))
      (node (ref "W5500-C4") (pin "1") (pinfunction "1_1") (pintype "passive"))
    )
    (net (code "113") (name "Net-(U2-EXRES1)") (class "Default")
      (node (ref "U2") (pin "10") (pinfunction "EXRES1_10") (pintype "passive"))
      (node (ref "W5500-R12") (pin "2") (pinfunction "2_2") (pintype "passive"))
    )
    (net (code "114") (name "Net-(U2-PMODE0)") (class "Default")
      (node (ref "U2") (pin "45") (pinfunction "PMODE0_45") (pintype "passive"))
      (node (ref "W5500-R3") (pin "2") (pinfunction "2_2") (pintype "passive"))
    )
    (net (code "115") (name "Net-(U2-PMODE1)") (class "Default")
      (node (ref "U2") (pin "44") (pinfunction "PMODE1_44") (pintype "passive"))
      (node (ref "W5500-R2") (pin "2") (pinfunction "2_2") (pintype "passive"))
    )
    (net (code "116") (name "Net-(U2-PMODE2)") (class "Default")
      (node (ref "U2") (pin "43") (pinfunction "PMODE2_43") (pintype "passive"))
      (node (ref "W5500-R1") (pin "2") (pinfunction "2_2") (pintype "passive"))
    )
    (net (code "117") (name "Net-(U2-RSVD-Pad23)") (class "Default")
      (node (ref "U2") (pin "23") (pinfunction "RSVD_23") (pintype "passive"))
      (node (ref "W5500-R11") (pin "2") (pinfunction "2_2") (pintype "passive"))
    )
    (net (code "118") (name "Net-(U2-RSVD-Pad38)") (class "Default")
      (node (ref "U2") (pin "38") (pinfunction "RSVD_38") (pintype "passive"))
      (node (ref "W5500-R8") (pin "1") (pinfunction "1_1") (pintype "passive"))
    )
    (net (code "119") (name "Net-(U2-RSVD-Pad39)") (class "Default")
      (node (ref "U2") (pin "39") (pinfunction "RSVD_39") (pintype "passive"))
      (node (ref "W5500-R7") (pin "1") (pinfunction "1_1") (pintype "passive"))
    )
    (net (code "120") (name "Net-(U2-RSVD-Pad40)") (class "Default")
      (node (ref "U2") (pin "40") (pinfunction "RSVD_40") (pintype "passive"))
      (node (ref "W5500-R6") (pin "1") (pinfunction "1_1") (pintype "passive"))
    )
    (net (code "121") (name "Net-(U2-RSVD-Pad41)") (class "Default")
      (node (ref "U2") (pin "41") (pinfunction "RSVD_41") (pintype "passive"))
      (node (ref "W5500-R5") (pin "1") (pinfunction "1_1") (pintype "passive"))
    )
    (net (code "122") (name "Net-(U2-RSVD-Pad42)") (class "Default")
      (node (ref "U2") (pin "42") (pinfunction "RSVD_42") (pintype "passive"))
      (node (ref "W5500-R4") (pin "1") (pinfunction "1_1") (pintype "passive"))
    )
    (net (code "123") (name "Net-(U2-TOCAP)") (class "Default")
      (node (ref "U2") (pin "20") (pinfunction "TOCAP_20") (pintype "passive"))
      (node (ref "W5500-C3") (pin "1") (pinfunction "1_1") (pintype "passive"))
    )
    (net (code "124") (name "Net-(U2-XI{slash}CLKIN)") (class "Default")
      (node (ref "U$3") (pin "P$1") (pinfunction "P$1_P$1") (pintype "bidirectional"))
      (node (ref "U2") (pin "30") (pinfunction "XI/CLKIN_30") (pintype "passive"))
      (node (ref "W5500-C1") (pin "1") (pinfunction "1_1") (pintype "passive"))
      (node (ref "W5500-R10") (pin "1") (pinfunction "1_1") (pintype "passive"))
      (node (ref "W5500-XTAL") (pin "1") (pinfunction "1_1") (pintype "passive"))
    )
    (net (code "125") (name "Net-(U2-XO)") (class "Default")
      (node (ref "U$3") (pin "P$2") (pinfunction "P$2_P$2") (pintype "bidirectional"))
      (node (ref "U2") (pin "31") (pinfunction "XO_31") (pintype "passive"))
      (node (ref "W5500-C2") (pin "1") (pinfunction "1_1") (pintype "passive"))
      (node (ref "W5500-R10") (pin "2") (pinfunction "2_2") (pintype "passive"))
      (node (ref "W5500-XTAL") (pin "2") (pinfunction "2_2") (pintype "passive"))
    )
    (net (code "126") (name "Q1") (class "Default")
      (node (ref "IC2") (pin "15") (pinfunction "QA_15") (pintype "tri_state"))
      (node (ref "SR_OUT1") (pin "3") (pinfunction "3_3") (pintype "passive"))
    )
    (net (code "127") (name "Q2") (class "Default")
      (node (ref "IC2") (pin "1") (pinfunction "QB_1") (pintype "tri_state"))
      (node (ref "SR_OUT1") (pin "4") (pinfunction "4_4") (pintype "passive"))
    )
    (net (code "128") (name "Q3") (class "Default")
      (node (ref "IC2") (pin "2") (pinfunction "QC_2") (pintype "tri_state"))
      (node (ref "SR_OUT1") (pin "5") (pinfunction "5_5") (pintype "passive"))
    )
    (net (code "129") (name "Q4") (class "Default")
      (node (ref "IC2") (pin "3") (pinfunction "QD_3") (pintype "tri_state"))
      (node (ref "SR_OUT1") (pin "6") (pinfunction "6_6") (pintype "passive"))
    )
    (net (code "130") (name "Q5") (class "Default")
      (node (ref "IC2") (pin "4") (pinfunction "QE_4") (pintype "tri_state"))
      (node (ref "SR_OUT1") (pin "7") (pinfunction "7_7") (pintype "passive"))
    )
    (net (code "131") (name "Q6") (class "Default")
      (node (ref "IC2") (pin "5") (pinfunction "QF_5") (pintype "tri_state"))
      (node (ref "SR_OUT1") (pin "8") (pinfunction "8_8") (pintype "passive"))
    )
    (net (code "132") (name "Q7") (class "Default")
      (node (ref "IC2") (pin "6") (pinfunction "QG_6") (pintype "tri_state"))
      (node (ref "SR_OUT1") (pin "9") (pinfunction "9_9") (pintype "passive"))
    )
    (net (code "133") (name "Q8") (class "Default")
      (node (ref "IC2") (pin "7") (pinfunction "QH_7") (pintype "tri_state"))
      (node (ref "SR_OUT1") (pin "10") (pinfunction "10_10") (pintype "passive"))
    )
    (net (code "134") (name "Q9") (class "Default")
      (node (ref "IC3") (pin "15") (pinfunction "QA_15") (pintype "tri_state"))
      (node (ref "SR_OUT2") (pin "3") (pinfunction "3_3") (pintype "passive"))
    )
    (net (code "135") (name "Q10") (class "Default")
      (node (ref "IC3") (pin "1") (pinfunction "QB_1") (pintype "tri_state"))
      (node (ref "SR_OUT2") (pin "4") (pinfunction "4_4") (pintype "passive"))
    )
    (net (code "136") (name "Q11") (class "Default")
      (node (ref "IC3") (pin "2") (pinfunction "QC_2") (pintype "tri_state"))
      (node (ref "SR_OUT2") (pin "5") (pinfunction "5_5") (pintype "passive"))
    )
    (net (code "137") (name "Q12") (class "Default")
      (node (ref "IC3") (pin "3") (pinfunction "QD_3") (pintype "tri_state"))
      (node (ref "SR_OUT2") (pin "6") (pinfunction "6_6") (pintype "passive"))
    )
    (net (code "138") (name "Q13") (class "Default")
      (node (ref "IC3") (pin "4") (pinfunction "QE_4") (pintype "tri_state"))
      (node (ref "SR_OUT2") (pin "7") (pinfunction "7_7") (pintype "passive"))
    )
    (net (code "139") (name "Q14") (class "Default")
      (node (ref "IC3") (pin "5") (pinfunction "QF_5") (pintype "tri_state"))
      (node (ref "SR_OUT2") (pin "8") (pinfunction "8_8") (pintype "passive"))
    )
    (net (code "140") (name "Q15") (class "Default")
      (node (ref "IC3") (pin "6") (pinfunction "QG_6") (pintype "tri_state"))
      (node (ref "SR_OUT2") (pin "9") (pinfunction "9_9") (pintype "passive"))
    )
    (net (code "141") (name "Q16") (class "Default")
      (node (ref "IC3") (pin "7") (pinfunction "QH_7") (pintype "tri_state"))
      (node (ref "SR_OUT2") (pin "10") (pinfunction "10_10") (pintype "passive"))
    )
    (net (code "142") (name "QS") (class "Default")
      (node (ref "IC2") (pin "9") (pinfunction "QH*_9") (pintype "tri_state"))
      (node (ref "IC3") (pin "14") (pinfunction "SER_14") (pintype "input"))
    )
    (net (code "143") (name "QS2") (class "Default")
      (node (ref "IC3") (pin "9") (pinfunction "QH*_9") (pintype "tri_state"))
      (node (ref "IC5") (pin "14") (pinfunction "SER_14") (pintype "input"))
    )
    (net (code "144") (name "RXN") (class "Default")
      (node (ref "ETH-C4") (pin "2") (pinfunction "2_2") (pintype "passive"))
      (node (ref "ETH-R7") (pin "1") (pinfunction "1_1") (pintype "passive"))
      (node (ref "U2") (pin "5") (pinfunction "RXN_5") (pintype "passive"))
    )
    (net (code "145") (name "RXP") (class "Default")
      (node (ref "ETH-C2") (pin "2") (pinfunction "2_2") (pintype "passive"))
      (node (ref "ETH-R6") (pin "2") (pinfunction "2_2") (pintype "passive"))
      (node (ref "U2") (pin "6") (pinfunction "RXP_6") (pintype "passive"))
    )
    (net (code "146") (name "SD_CS") (class "Default")
      (node (ref "STM_CHIP") (pin "53") (pinfunction "PC12_53") (pintype "bidirectional"))
      (node (ref "U$4") (pin "SD_CS") (pinfunction "SD_CS_SD_CS") (pintype "passive"))
    )
    (net (code "147") (name "SERIAL_RX") (class "Default")
      (node (ref "STM-USART") (pin "3") (pinfunction "3_3") (pintype "passive"))
      (node (ref "STM_CHIP") (pin "43") (pinfunction "PA10_43") (pintype "bidirectional"))
    )
    (net (code "148") (name "SERIAL_TX") (class "Default")
      (node (ref "STM-USART") (pin "2") (pinfunction "2_2") (pintype "passive"))
      (node (ref "STM_CHIP") (pin "42") (pinfunction "PA9_42") (pintype "bidirectional"))
    )
    (net (code "149") (name "SIM900_PWRKEY") (class "Default")
      (node (ref "IC1") (pin "P$1") (pinfunction "PWRKEY_P$1") (pintype "power_in"))
      (node (ref "SIM900-T3") (pin "C") (pinfunction "C_C") (pintype "passive"))
    )
    (net (code "150") (name "SIM900_RESET") (class "Default")
      (node (ref "IC1") (pin "P$16") (pinfunction "NRESET_P$16") (pintype "bidirectional"))
      (node (ref "SIM900-T4") (pin "C") (pinfunction "C_C") (pintype "passive"))
    )
    (net (code "151") (name "SIM_NETLIGHT") (class "Default")
      (node (ref "IC1") (pin "P$52") (pinfunction "NETLIGHT_P$52") (pintype "bidirectional"))
      (node (ref "SIM900-R8") (pin "2") (pinfunction "2_2") (pintype "passive"))
    )
    (net (code "152") (name "SIM_PWRKEY") (class "Default")
      (node (ref "SIM900-R10") (pin "1") (pinfunction "1_1") (pintype "passive"))
      (node (ref "STM_CHIP") (pin "40") (pinfunction "PC9_40") (pintype "bidirectional"))
    )
    (net (code "153") (name "SIM_RESET") (class "Default")
      (node (ref "SIM900-R11") (pin "1") (pinfunction "1_1") (pintype "passive"))
      (node (ref "STM_CHIP") (pin "50") (pinfunction "PA15_50") (pintype "bidirectional"))
    )
    (net (code "154") (name "SIM_RX") (class "Default")
      (node (ref "IC1") (pin "P$10") (pinfunction "RXD_P$10") (pintype "input"))
      (node (ref "STM_CHIP") (pin "51") (pinfunction "PC10_51") (pintype "bidirectional"))
    )
    (net (code "155") (name "SIM_STATUS") (class "Default")
      (node (ref "IC1") (pin "P$66") (pinfunction "STATUS_P$66") (pintype "bidirectional"))
      (node (ref "SIM900-R5") (pin "2") (pinfunction "2_2") (pintype "passive"))
    )
    (net (code "156") (name "SIM_TX") (class "Default")
      (node (ref "IC1") (pin "P$9") (pinfunction "TXD_P$9") (pintype "output"))
      (node (ref "STM_CHIP") (pin "52") (pinfunction "PC11_52") (pintype "bidirectional"))
    )
    (net (code "157") (name "SR_DS") (class "Default")
      (node (ref "IC2") (pin "14") (pinfunction "SER_14") (pintype "input"))
      (node (ref "STM_CHIP") (pin "8") (pinfunction "PC0_8") (pintype "bidirectional"))
    )
    (net (code "158") (name "SR_RST") (class "Default")
      (node (ref "IC2") (pin "10") (pinfunction "SCL_10") (pintype "input"))
      (node (ref "IC3") (pin "10") (pinfunction "SCL_10") (pintype "input"))
      (node (ref "IC5") (pin "10") (pinfunction "SCL_10") (pintype "input"))
      (node (ref "STM_CHIP") (pin "11") (pinfunction "PC3_11") (pintype "bidirectional"))
    )
    (net (code "159") (name "SR_SHCP") (class "Default")
      (node (ref "IC2") (pin "11") (pinfunction "SCK_11") (pintype "input"))
      (node (ref "IC3") (pin "11") (pinfunction "SCK_11") (pintype "input"))
      (node (ref "IC5") (pin "11") (pinfunction "SCK_11") (pintype "input"))
      (node (ref "STM_CHIP") (pin "10") (pinfunction "PC2_10") (pintype "bidirectional"))
    )
    (net (code "160") (name "SR_STCP") (class "Default")
      (node (ref "IC2") (pin "12") (pinfunction "RCK_12") (pintype "input"))
      (node (ref "IC3") (pin "12") (pinfunction "RCK_12") (pintype "input"))
      (node (ref "IC5") (pin "12") (pinfunction "RCK_12") (pintype "input"))
      (node (ref "STM_CHIP") (pin "9") (pinfunction "PC1_9") (pintype "bidirectional"))
    )
    (net (code "161") (name "SWD_NRST") (class "Default")
      (node (ref "S1") (pin "1") (pinfunction "1_1") (pintype "passive"))
      (node (ref "S1") (pin "2") (pinfunction "2_2") (pintype "passive"))
      (node (ref "STM-C8") (pin "1") (pinfunction "1_1") (pintype "passive"))
      (node (ref "STM_CHIP") (pin "7") (pinfunction "NRST_7") (pintype "bidirectional"))
    )
    (net (code "162") (name "SWD_TCK") (class "Default")
      (node (ref "STM-SWD") (pin "2") (pinfunction "2_2") (pintype "passive"))
      (node (ref "STM_CHIP") (pin "49") (pinfunction "PA14_49") (pintype "bidirectional"))
    )
    (net (code "163") (name "SWD_TMS") (class "Default")
      (node (ref "STM-SWD") (pin "4") (pinfunction "4_4") (pintype "passive"))
      (node (ref "STM_CHIP") (pin "46") (pinfunction "PA13_46") (pintype "bidirectional"))
    )
    (net (code "164") (name "SW_PIN") (class "Default")
      (node (ref "STM_CHIP") (pin "30") (pinfunction "PB11_30") (pintype "bidirectional"))
      (node (ref "U$6") (pin "3") (pinfunction "4_3") (pintype "passive"))
    )
    (net (code "165") (name "TXN") (class "Default")
      (node (ref "ETH-R2") (pin "1") (pinfunction "1_1") (pintype "passive"))
      (node (ref "ETHERNET") (pin "2") (pinfunction "TX-_2") (pintype "bidirectional"))
      (node (ref "U2") (pin "1") (pinfunction "TXN_1") (pintype "passive"))
    )
    (net (code "166") (name "TXP") (class "Default")
      (node (ref "ETH-R1") (pin "1") (pinfunction "1_1") (pintype "passive"))
      (node (ref "ETHERNET") (pin "1") (pinfunction "TX+_1") (pintype "bidirectional"))
      (node (ref "U2") (pin "2") (pinfunction "TXP_2") (pintype "passive"))
    )
    (net (code "167") (name "USIM_CLK") (class "Default")
      (node (ref "SIM900-R2") (pin "2") (pinfunction "2_2") (pintype "passive"))
      (node (ref "U$8") (pin "SIM_CLK") (pinfunction "SIM_CLK_SIM_CLK") (pintype "bidirectional"))
    )
    (net (code "168") (name "USIM_DATA") (class "Default")
      (node (ref "SIM900-R3") (pin "2") (pinfunction "2_2") (pintype "passive"))
      (node (ref "U$8") (pin "SIM_IO") (pinfunction "SIM_IO_SIM_IO") (pintype "bidirectional"))
    )
    (net (code "169") (name "USIM_RESET") (class "Default")
      (node (ref "SIM900-R1") (pin "2") (pinfunction "2_2") (pintype "passive"))
      (node (ref "U$8") (pin "SIM_RST") (pinfunction "SIM_RST_SIM_RST") (pintype "bidirectional"))
    )
    (net (code "170") (name "USIM_VCC") (class "Default")
      (node (ref "IC1") (pin "P$30") (pinfunction "SIM_VDD_P$30") (pintype "power_in"))
      (node (ref "SIM900-C4") (pin "1") (pinfunction "1_1") (pintype "passive"))
      (node (ref "SIM900-C5") (pin "1") (pinfunction "1_1") (pintype "passive"))
      (node (ref "SIM_C1") (pin "2") (pinfunction "2_2") (pintype "passive"))
      (node (ref "SIM_C2") (pin "2") (pinfunction "2_2") (pintype "passive"))
      (node (ref "U$8") (pin "SIM_VDD") (pinfunction "SIM_VDD_SIM_VDD") (pintype "bidirectional"))
    )
    (net (code "171") (name "VBAT") (class "Default")
      (node (ref "BAT1") (pin "1") (pinfunction "+_1") (pintype "power_in"))
      (node (ref "STM_CHIP") (pin "1") (pinfunction "VLCD_1") (pintype "power_in"))
    )
    (net (code "172") (name "VCC") (class "Default")
      (node (ref "ETH-R1") (pin "2") (pinfunction "2_2") (pintype "passive"))
      (node (ref "ETH-R2") (pin "2") (pinfunction "2_2") (pintype "passive"))
      (node (ref "ETH-R3") (pin "2") (pinfunction "2_2") (pintype "passive"))
      (node (ref "STM-C9") (pin "1") (pinfunction "1_1") (pintype "passive"))
      (node (ref "STM-L1") (pin "2") (pinfunction "2_2") (pintype "passive"))
      (node (ref "STM_CHIP") (pin "13") (pinfunction "VDDA_13") (pintype "power_in"))
      (node (ref "SYS-C4") (pin "1") (pinfunction "1_1") (pintype "passive"))
      (node (ref "SYS-R2") (pin "2") (pinfunction "2_2") (pintype "passive"))
      (node (ref "U2") (pin "11") (pinfunction "AVDD_11") (pintype "passive"))
      (node (ref "U2") (pin "15") (pinfunction "AVDD_15") (pintype "passive"))
      (node (ref "U2") (pin "17") (pinfunction "AVDD_17") (pintype "passive"))
      (node (ref "U2") (pin "21") (pinfunction "AVDD_21") (pintype "passive"))
      (node (ref "U2") (pin "4") (pinfunction "AVDD_4") (pintype "passive"))
      (node (ref "U2") (pin "8") (pinfunction "AVDD_8") (pintype "passive"))
      (node (ref "W5500-C10") (pin "1") (pinfunction "1_1") (pintype "passive"))
      (node (ref "W5500-C11") (pin "1") (pinfunction "1_1") (pintype "passive"))
      (node (ref "W5500-C12") (pin "+") (pinfunction "+_+") (pintype "passive"))
      (node (ref "W5500-C6") (pin "1") (pinfunction "1_1") (pintype "passive"))
      (node (ref "W5500-C7") (pin "1") (pinfunction "1_1") (pintype "passive"))
      (node (ref "W5500-C8") (pin "1") (pinfunction "1_1") (pintype "passive"))
      (node (ref "W5500-C9") (pin "1") (pinfunction "1_1") (pintype "passive"))
    )
    (net (code "173") (name "VDD") (class "Default")
      (node (ref "DHT-R1") (pin "1") (pinfunction "1_1") (pintype "passive"))
      (node (ref "ESP-VDD") (pin "1") (pinfunction "1_1") (pintype "passive"))
      (node (ref "ETHERNET") (pin "12") (pinfunction "LED2_A_12") (pintype "bidirectional"))
      (node (ref "ETHERNET") (pin "9") (pinfunction "LED1_A_9") (pintype "bidirectional"))
      (node (ref "IC2") (pin "16") (pinfunction "VCC_16") (pintype "power_in"))
      (node (ref "IC3") (pin "16") (pinfunction "VCC_16") (pintype "power_in"))
      (node (ref "IC5") (pin "16") (pinfunction "VCC_16") (pintype "power_in"))
      (node (ref "LCD-R1") (pin "2") (pinfunction "2_2") (pintype "passive"))
      (node (ref "PWR-SWT") (pin "1") (pinfunction "1_1") (pintype "passive"))
      (node (ref "R1") (pin "1") (pinfunction "1_1") (pintype "passive"))
      (node (ref "SENSOR-DHT") (pin "1") (pinfunction "1_1") (pintype "passive"))
      (node (ref "SIM900-R4") (pin "2") (pinfunction "2_2") (pintype "passive"))
      (node (ref "SIM900-R7") (pin "2") (pinfunction "2_2") (pintype "passive"))
      (node (ref "STM-C1") (pin "2") (pinfunction "2_2") (pintype "passive"))
      (node (ref "STM-C10") (pin "1") (pinfunction "1_1") (pintype "passive"))
      (node (ref "STM-C11") (pin "1") (pinfunction "1_1") (pintype "passive"))
      (node (ref "STM-C12") (pin "1") (pinfunction "1_1") (pintype "passive"))
      (node (ref "STM-C13") (pin "1") (pinfunction "1_1") (pintype "passive"))
      (node (ref "STM-L1") (pin "1") (pinfunction "1_1") (pintype "passive"))
      (node (ref "STM-SWD") (pin "1") (pinfunction "1_1") (pintype "passive"))
      (node (ref "STM-USART") (pin "1") (pinfunction "1_1") (pintype "passive"))
      (node (ref "STM_CHIP") (pin "19") (pinfunction "VDD_4_19") (pintype "power_in"))
      (node (ref "STM_CHIP") (pin "32") (pinfunction "VDD_1_32") (pintype "power_in"))
      (node (ref "STM_CHIP") (pin "48") (pinfunction "VDD_2_48") (pintype "power_in"))
      (node (ref "STM_CHIP") (pin "64") (pinfunction "VDD_3_64") (pintype "power_in"))
      (node (ref "SYS-C3") (pin "1") (pinfunction "1_1") (pintype "passive"))
      (node (ref "SYS-L2") (pin "2") (pinfunction "2_2") (pintype "passive"))
      (node (ref "SYS-R2") (pin "1") (pinfunction "1_1") (pintype "passive"))
      (node (ref "U$4") (pin "LCD_VCC") (pinfunction "LCD_VCC_LCD_VCC") (pintype "passive"))
      (node (ref "U2") (pin "28") (pinfunction "VDD_28") (pintype "passive"))
      (node (ref "W5500-C13") (pin "+") (pinfunction "+_+") (pintype "passive"))
      (node (ref "W5500-C5") (pin "1") (pinfunction "1_1") (pintype "passive"))
      (node (ref "W5500-R1") (pin "1") (pinfunction "1_1") (pintype "passive"))
      (node (ref "W5500-R13") (pin "2") (pinfunction "2_2") (pintype "passive"))
      (node (ref "W5500-R2") (pin "1") (pinfunction "1_1") (pintype "passive"))
      (node (ref "W5500-R3") (pin "1") (pinfunction "1_1") (pintype "passive"))
      (node (ref "W5500-R9") (pin "2") (pinfunction "2_2") (pintype "passive"))
    )
    (net (code "174") (name "VESP") (class "Default")
      (node (ref "ESP-C1") (pin "1") (pinfunction "1_1") (pintype "passive"))
      (node (ref "ESP-GPIO0") (pin "1") (pinfunction "1_1") (pintype "passive"))
      (node (ref "ESP-VDD") (pin "2") (pinfunction "2_2") (pintype "passive"))
      (node (ref "U$5") (pin "CH_PD") (pinfunction "CH_PD_CH_PD") (pintype "bidirectional"))
      (node (ref "U$5") (pin "VCC") (pinfunction "VCC_VCC") (pintype "power_in"))
    )
    (net (code "175") (name "VEXT") (class "Default")
      (node (ref "ESP-UART-A") (pin "1") (pinfunction "1_1") (pintype "passive"))
      (node (ref "ESP-VDD") (pin "3") (pinfunction "3_3") (pintype "passive"))
    )
    (net (code "176") (name "unconnected-(IC1-ADC-PadP$25)") (class "Default")
      (node (ref "IC1") (pin "P$25") (pinfunction "ADC_P$25") (pintype "bidirectional"))
    )
    (net (code "177") (name "unconnected-(IC1-CTS-PadP$7)") (class "Default")
      (node (ref "IC1") (pin "P$7") (pinfunction "CTS_P$7") (pintype "output"))
    )
    (net (code "178") (name "unconnected-(IC1-DBG_RXD-PadP$28)") (class "Default")
      (node (ref "IC1") (pin "P$28") (pinfunction "DBG_RXD_P$28") (pintype "input"))
    )
    (net (code "179") (name "unconnected-(IC1-DBG_TXD-PadP$27)") (class "Default")
      (node (ref "IC1") (pin "P$27") (pinfunction "DBG_TXD_P$27") (pintype "output"))
    )
    (net (code "180") (name "unconnected-(IC1-DCD-PadP$5)") (class "Default")
      (node (ref "IC1") (pin "P$5") (pinfunction "DCD_P$5") (pintype "output"))
    )
    (net (code "181") (name "unconnected-(IC1-DISP_CLK-PadP$11)") (class "Default")
      (node (ref "IC1") (pin "P$11") (pinfunction "DISP_CLK_P$11") (pintype "bidirectional"))
    )
    (net (code "182") (name "unconnected-(IC1-DISP_CS-PadP$14)") (class "Default")
      (node (ref "IC1") (pin "P$14") (pinfunction "DISP_CS_P$14") (pintype "bidirectional"))
    )
    (net (code "183") (name "unconnected-(IC1-DISP_DATA-PadP$12)") (class "Default")
      (node (ref "IC1") (pin "P$12") (pinfunction "DISP_DATA_P$12") (pintype "bidirectional"))
    )
    (net (code "184") (name "unconnected-(IC1-DISP_DC-PadP$13)") (class "Default")
      (node (ref "IC1") (pin "P$13") (pinfunction "DISP_DC_P$13") (pintype "bidirectional"))
    )
    (net (code "185") (name "unconnected-(IC1-DTR-PadP$3)") (class "Default")
      (node (ref "IC1") (pin "P$3") (pinfunction "DTR_P$3") (pintype "input"))
    )
    (net (code "186") (name "unconnected-(IC1-GPIO1{slash}KBR4-PadP$40)") (class "Default")
      (node (ref "IC1") (pin "P$40") (pinfunction "GPIO1/KBR4_P$40") (pintype "bidirectional"))
    )
    (net (code "187") (name "unconnected-(IC1-GPIO2{slash}KBR3-PadP$41)") (class "Default")
      (node (ref "IC1") (pin "P$41") (pinfunction "GPIO2/KBR3_P$41") (pintype "bidirectional"))
    )
    (net (code "188") (name "unconnected-(IC1-GPIO3{slash}KBR2-PadP$42)") (class "Default")
      (node (ref "IC1") (pin "P$42") (pinfunction "GPIO3/KBR2_P$42") (pintype "bidirectional"))
    )
    (net (code "189") (name "unconnected-(IC1-GPIO4{slash}KBR1-PadP$43)") (class "Default")
      (node (ref "IC1") (pin "P$43") (pinfunction "GPIO4/KBR1_P$43") (pintype "bidirectional"))
    )
    (net (code "190") (name "unconnected-(IC1-GPIO5{slash}KBR0-PadP$44)") (class "Default")
      (node (ref "IC1") (pin "P$44") (pinfunction "GPIO5/KBR0_P$44") (pintype "bidirectional"))
    )
    (net (code "191") (name "unconnected-(IC1-GPIO6{slash}KBC4-PadP$47)") (class "Default")
      (node (ref "IC1") (pin "P$47") (pinfunction "GPIO6/KBC4_P$47") (pintype "bidirectional"))
    )
    (net (code "192") (name "unconnected-(IC1-GPIO7{slash}KBC3-PadP$48)") (class "Default")
      (node (ref "IC1") (pin "P$48") (pinfunction "GPIO7/KBC3_P$48") (pintype "bidirectional"))
    )
    (net (code "193") (name "unconnected-(IC1-GPIO8{slash}KBC2-PadP$49)") (class "Default")
      (node (ref "IC1") (pin "P$49") (pinfunction "GPIO8/KBC2_P$49") (pintype "bidirectional"))
    )
    (net (code "194") (name "unconnected-(IC1-GPIO9{slash}KBC1-PadP$50)") (class "Default")
      (node (ref "IC1") (pin "P$50") (pinfunction "GPIO9/KBC1_P$50") (pintype "bidirectional"))
    )
    (net (code "195") (name "unconnected-(IC1-GPIO10-PadP$51)") (class "Default")
      (node (ref "IC1") (pin "P$51") (pinfunction "GPIO10_P$51") (pintype "bidirectional"))
    )
    (net (code "196") (name "unconnected-(IC1-LINEIN_L-PadP$24)") (class "Default")
      (node (ref "IC1") (pin "P$24") (pinfunction "LINEIN_L_P$24") (pintype "bidirectional"))
    )
    (net (code "197") (name "unconnected-(IC1-LINEIN_R-PadP$23)") (class "Default")
      (node (ref "IC1") (pin "P$23") (pinfunction "LINEIN_R_P$23") (pintype "bidirectional"))
    )
    (net (code "198") (name "unconnected-(IC1-MIC_N-PadP$20)") (class "Default")
      (node (ref "IC1") (pin "P$20") (pinfunction "MIC_N_P$20") (pintype "bidirectional"))
    )
    (net (code "199") (name "unconnected-(IC1-MIC_P-PadP$19)") (class "Default")
      (node (ref "IC1") (pin "P$19") (pinfunction "MIC_P_P$19") (pintype "bidirectional"))
    )
    (net (code "200") (name "unconnected-(IC1-NC-PadP$2)") (class "Default")
      (node (ref "IC1") (pin "P$2") (pinfunction "NC_P$2") (pintype "no_connect"))
    )
    (net (code "201") (name "unconnected-(IC1-NC-PadP$6)") (class "Default")
      (node (ref "IC1") (pin "P$6") (pinfunction "NC_P$6") (pintype "no_connect"))
    )
    (net (code "202") (name "unconnected-(IC1-PWM1-PadP$35)") (class "Default")
      (node (ref "IC1") (pin "P$35") (pinfunction "PWM1_P$35") (pintype "bidirectional"))
    )
    (net (code "203") (name "unconnected-(IC1-PWM2-PadP$36)") (class "Default")
      (node (ref "IC1") (pin "P$36") (pinfunction "PWM2_P$36") (pintype "bidirectional"))
    )
    (net (code "204") (name "unconnected-(IC1-RI-PadP$4)") (class "Default")
      (node (ref "IC1") (pin "P$4") (pinfunction "RI_P$4") (pintype "output"))
    )
    (net (code "205") (name "unconnected-(IC1-RTS-PadP$8)") (class "Default")
      (node (ref "IC1") (pin "P$8") (pinfunction "RTS_P$8") (pintype "input"))
    )
    (net (code "206") (name "unconnected-(IC1-SCL-PadP$38)") (class "Default")
      (node (ref "IC1") (pin "P$38") (pinfunction "SCL_P$38") (pintype "bidirectional"))
    )
    (net (code "207") (name "unconnected-(IC1-SDA-PadP$37)") (class "Default")
      (node (ref "IC1") (pin "P$37") (pinfunction "SDA_P$37") (pintype "bidirectional"))
    )
    (net (code "208") (name "unconnected-(IC1-SIM_PRESENCE-PadP$34)") (class "Default")
      (node (ref "IC1") (pin "P$34") (pinfunction "SIM_PRESENCE_P$34") (pintype "bidirectional"))
    )
    (net (code "209") (name "unconnected-(IC1-SPK_N-PadP$22)") (class "Default")
      (node (ref "IC1") (pin "P$22") (pinfunction "SPK_N_P$22") (pintype "bidirectional"))
    )
    (net (code "210") (name "unconnected-(IC1-SPK_P-PadP$21)") (class "Default")
      (node (ref "IC1") (pin "P$21") (pinfunction "SPK_P_P$21") (pintype "bidirectional"))
    )
    (net (code "211") (name "unconnected-(IC1-VDD_EXT-PadP$15)") (class "Default")
      (node (ref "IC1") (pin "P$15") (pinfunction "VDD_EXT_P$15") (pintype "bidirectional"))
    )
    (net (code "212") (name "unconnected-(IC5A-QE-Pad4)") (class "Default")
      (node (ref "IC5") (pin "4") (pinfunction "QE_4") (pintype "tri_state"))
    )
    (net (code "213") (name "unconnected-(IC5A-QF-Pad5)") (class "Default")
      (node (ref "IC5") (pin "5") (pinfunction "QF_5") (pintype "tri_state"))
    )
    (net (code "214") (name "unconnected-(IC5A-QG-Pad6)") (class "Default")
      (node (ref "IC5") (pin "6") (pinfunction "QG_6") (pintype "tri_state"))
    )
    (net (code "215") (name "unconnected-(IC5A-QH*-Pad9)") (class "Default")
      (node (ref "IC5") (pin "9") (pinfunction "QH*_9") (pintype "tri_state"))
    )
    (net (code "216") (name "unconnected-(IC5A-QH-Pad7)") (class "Default")
      (node (ref "IC5") (pin "7") (pinfunction "QH_7") (pintype "tri_state"))
    )
    (net (code "217") (name "unconnected-(SENSOR-DHT-Pad3)") (class "Default")
      (node (ref "SENSOR-DHT") (pin "3") (pinfunction "3_3") (pintype "passive"))
    )
    (net (code "218") (name "unconnected-(STM_CHIP-BOOT0-Pad60)") (class "Default")
      (node (ref "STM_CHIP") (pin "60") (pinfunction "BOOT0_60") (pintype "input"))
    )
    (net (code "219") (name "unconnected-(STM_CHIP-PA0-WKUP1-Pad14)") (class "Default")
      (node (ref "STM_CHIP") (pin "14") (pinfunction "PA0-WKUP1_14") (pintype "bidirectional"))
    )
    (net (code "220") (name "unconnected-(STM_CHIP-PA8-Pad41)") (class "Default")
      (node (ref "STM_CHIP") (pin "41") (pinfunction "PA8_41") (pintype "bidirectional"))
    )
    (net (code "221") (name "unconnected-(STM_CHIP-PA11-Pad44)") (class "Default")
      (node (ref "STM_CHIP") (pin "44") (pinfunction "PA11_44") (pintype "bidirectional"))
    )
    (net (code "222") (name "unconnected-(STM_CHIP-PA12-Pad45)") (class "Default")
      (node (ref "STM_CHIP") (pin "45") (pinfunction "PA12_45") (pintype "bidirectional"))
    )
    (net (code "223") (name "unconnected-(STM_CHIP-PB2-Pad28)") (class "Default")
      (node (ref "STM_CHIP") (pin "28") (pinfunction "PB2_28") (pintype "bidirectional"))
    )
    (net (code "224") (name "unconnected-(STM_CHIP-PB3-Pad55)") (class "Default")
      (node (ref "STM_CHIP") (pin "55") (pinfunction "PB3_55") (pintype "bidirectional"))
    )
    (net (code "225") (name "unconnected-(STM_CHIP-PC7-Pad38)") (class "Default")
      (node (ref "STM_CHIP") (pin "38") (pinfunction "PC7_38") (pintype "bidirectional"))
    )
    (net (code "226") (name "unconnected-(STM_CHIP-PC13-RTC_AF1-WKUP2-Pad2)") (class "Default")
      (node (ref "STM_CHIP") (pin "2") (pinfunction "PC13-RTC_AF1-WKUP2_2") (pintype "bidirectional"))
    )
    (net (code "227") (name "unconnected-(STM_CHIP-PH0_-OSC_IN-Pad5)") (class "Default")
      (node (ref "STM_CHIP") (pin "5") (pinfunction "PH0_-OSC_IN_5") (pintype "bidirectional"))
    )
    (net (code "228") (name "unconnected-(STM_CHIP-PH1-_OSC_OUT-Pad6)") (class "Default")
      (node (ref "STM_CHIP") (pin "6") (pinfunction "PH1-_OSC_OUT_6") (pintype "bidirectional"))
    )
    (net (code "229") (name "unconnected-(U$5-GPIO2-PadGPIO02)") (class "Default")
      (node (ref "U$5") (pin "GPIO02") (pinfunction "GPIO2_GPIO02") (pintype "bidirectional"))
    )
    (net (code "230") (name "unconnected-(U$5-GPIO4-PadGPIO04)") (class "Default")
      (node (ref "U$5") (pin "GPIO04") (pinfunction "GPIO4_GPIO04") (pintype "bidirectional"))
    )
    (net (code "231") (name "unconnected-(U$5-GPIO5-PadGPIO05)") (class "Default")
      (node (ref "U$5") (pin "GPIO05") (pinfunction "GPIO5_GPIO05") (pintype "bidirectional"))
    )
    (net (code "232") (name "unconnected-(U$5-PadADC)") (class "Default")
      (node (ref "U$5") (pin "ADC") (pinfunction "ADC_ADC") (pintype "bidirectional"))
    )
    (net (code "233") (name "unconnected-(U$5-PadGPIO12)") (class "Default")
      (node (ref "U$5") (pin "GPIO12") (pinfunction "GPIO12_GPIO12") (pintype "bidirectional"))
    )
    (net (code "234") (name "unconnected-(U$5-PadGPIO13)") (class "Default")
      (node (ref "U$5") (pin "GPIO13") (pinfunction "GPIO13_GPIO13") (pintype "bidirectional"))
    )
    (net (code "235") (name "unconnected-(U$5-PadGPIO14)") (class "Default")
      (node (ref "U$5") (pin "GPIO14") (pinfunction "GPIO14_GPIO14") (pintype "bidirectional"))
    )
    (net (code "236") (name "unconnected-(U$5-PadGPIO16)") (class "Default")
      (node (ref "U$5") (pin "GPIO16") (pinfunction "GPIO16_GPIO16") (pintype "bidirectional"))
    )
    (net (code "237") (name "unconnected-(U$5-PadREST)") (class "Default")
      (node (ref "U$5") (pin "REST") (pinfunction "REST_REST") (pintype "bidirectional"))
    )
    (net (code "238") (name "unconnected-(U$8-PadVPP)") (class "Default")
      (node (ref "U$8") (pin "VPP") (pinfunction "VPP_VPP") (pintype "bidirectional"))
    )
    (net (code "239") (name "unconnected-(U2-DNC-Pad7)") (class "Default")
      (node (ref "U2") (pin "7") (pinfunction "DNC_7") (pintype "passive"))
    )
    (net (code "240") (name "unconnected-(U2-DUPLED-Pad26)") (class "Default")
      (node (ref "U2") (pin "26") (pinfunction "DUPLED_26") (pintype "passive"))
    )
    (net (code "241") (name "unconnected-(U2-INT_N-Pad36)") (class "Default")
      (node (ref "U2") (pin "36") (pinfunction "INT_N_36") (pintype "passive"))
    )
    (net (code "242") (name "unconnected-(U2-NC-Pad12)") (class "Default")
      (node (ref "U2") (pin "12") (pinfunction "NC_12") (pintype "passive"))
    )
    (net (code "243") (name "unconnected-(U2-NC-Pad13)") (class "Default")
      (node (ref "U2") (pin "13") (pinfunction "NC_13") (pintype "passive"))
    )
    (net (code "244") (name "unconnected-(U2-NC-Pad46)") (class "Default")
      (node (ref "U2") (pin "46") (pinfunction "NC_46") (pintype "passive"))
    )
    (net (code "245") (name "unconnected-(U2-NC-Pad47)") (class "Default")
      (node (ref "U2") (pin "47") (pinfunction "NC_47") (pintype "passive"))
    )
    (net (code "246") (name "unconnected-(U2-SPDLED-Pad24)") (class "Default")
      (node (ref "U2") (pin "24") (pinfunction "SPDLED_24") (pintype "passive"))
    )
    (net (code "247") (name "unconnected-(U2-VBG-Pad18)") (class "Default")
      (node (ref "U2") (pin "18") (pinfunction "VBG_18") (pintype "passive"))
    )
  )
)
